# uLements_v2_5.net
KiCad netlist of a schematic drawn in EAGLE
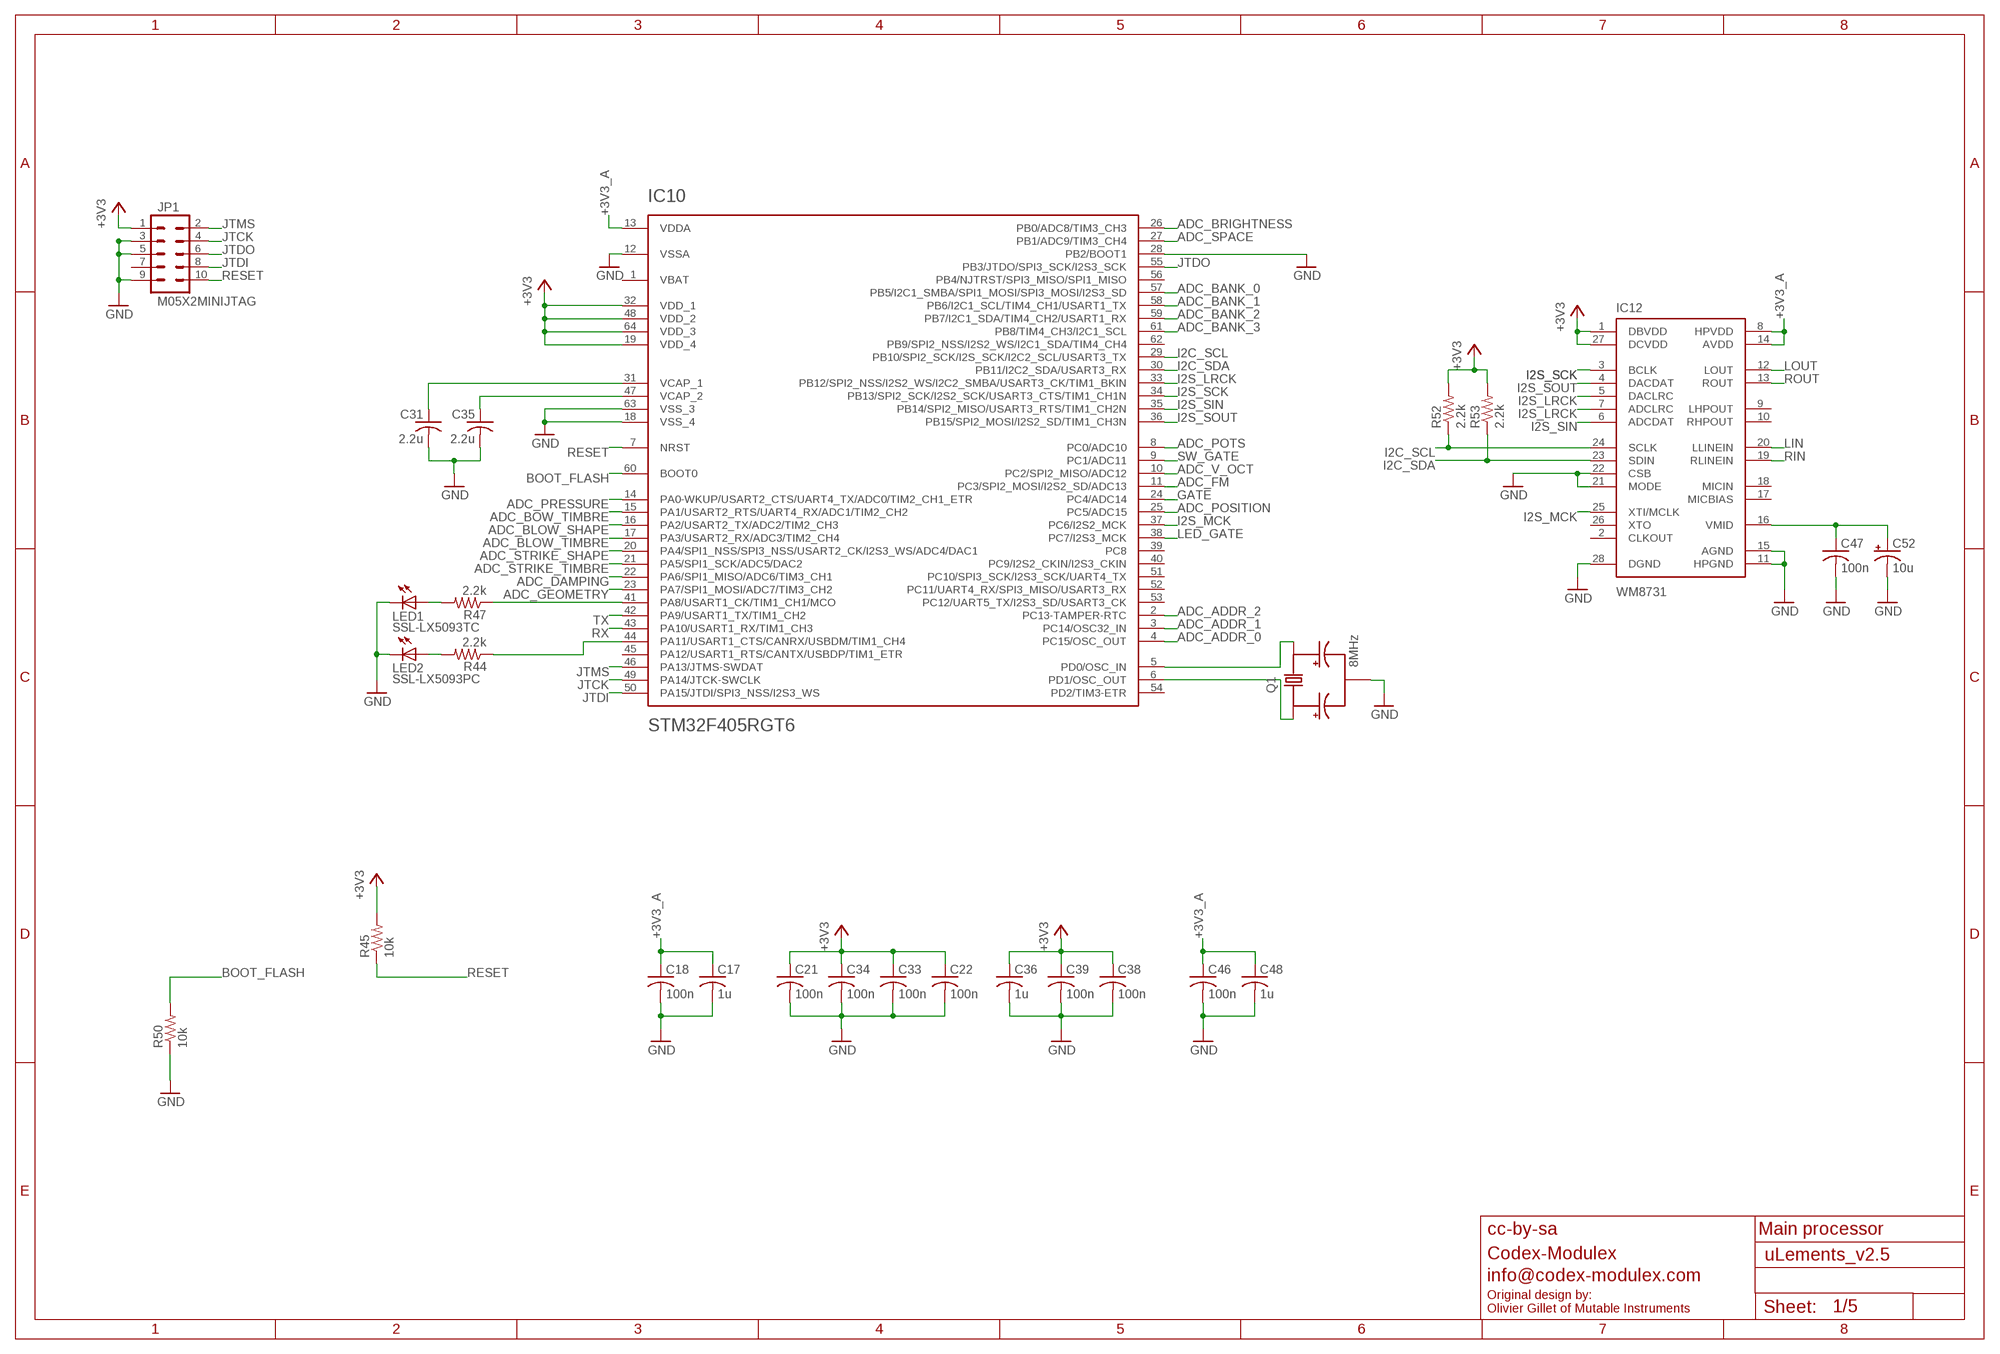
[diagram p0: schematic, sheet 1]
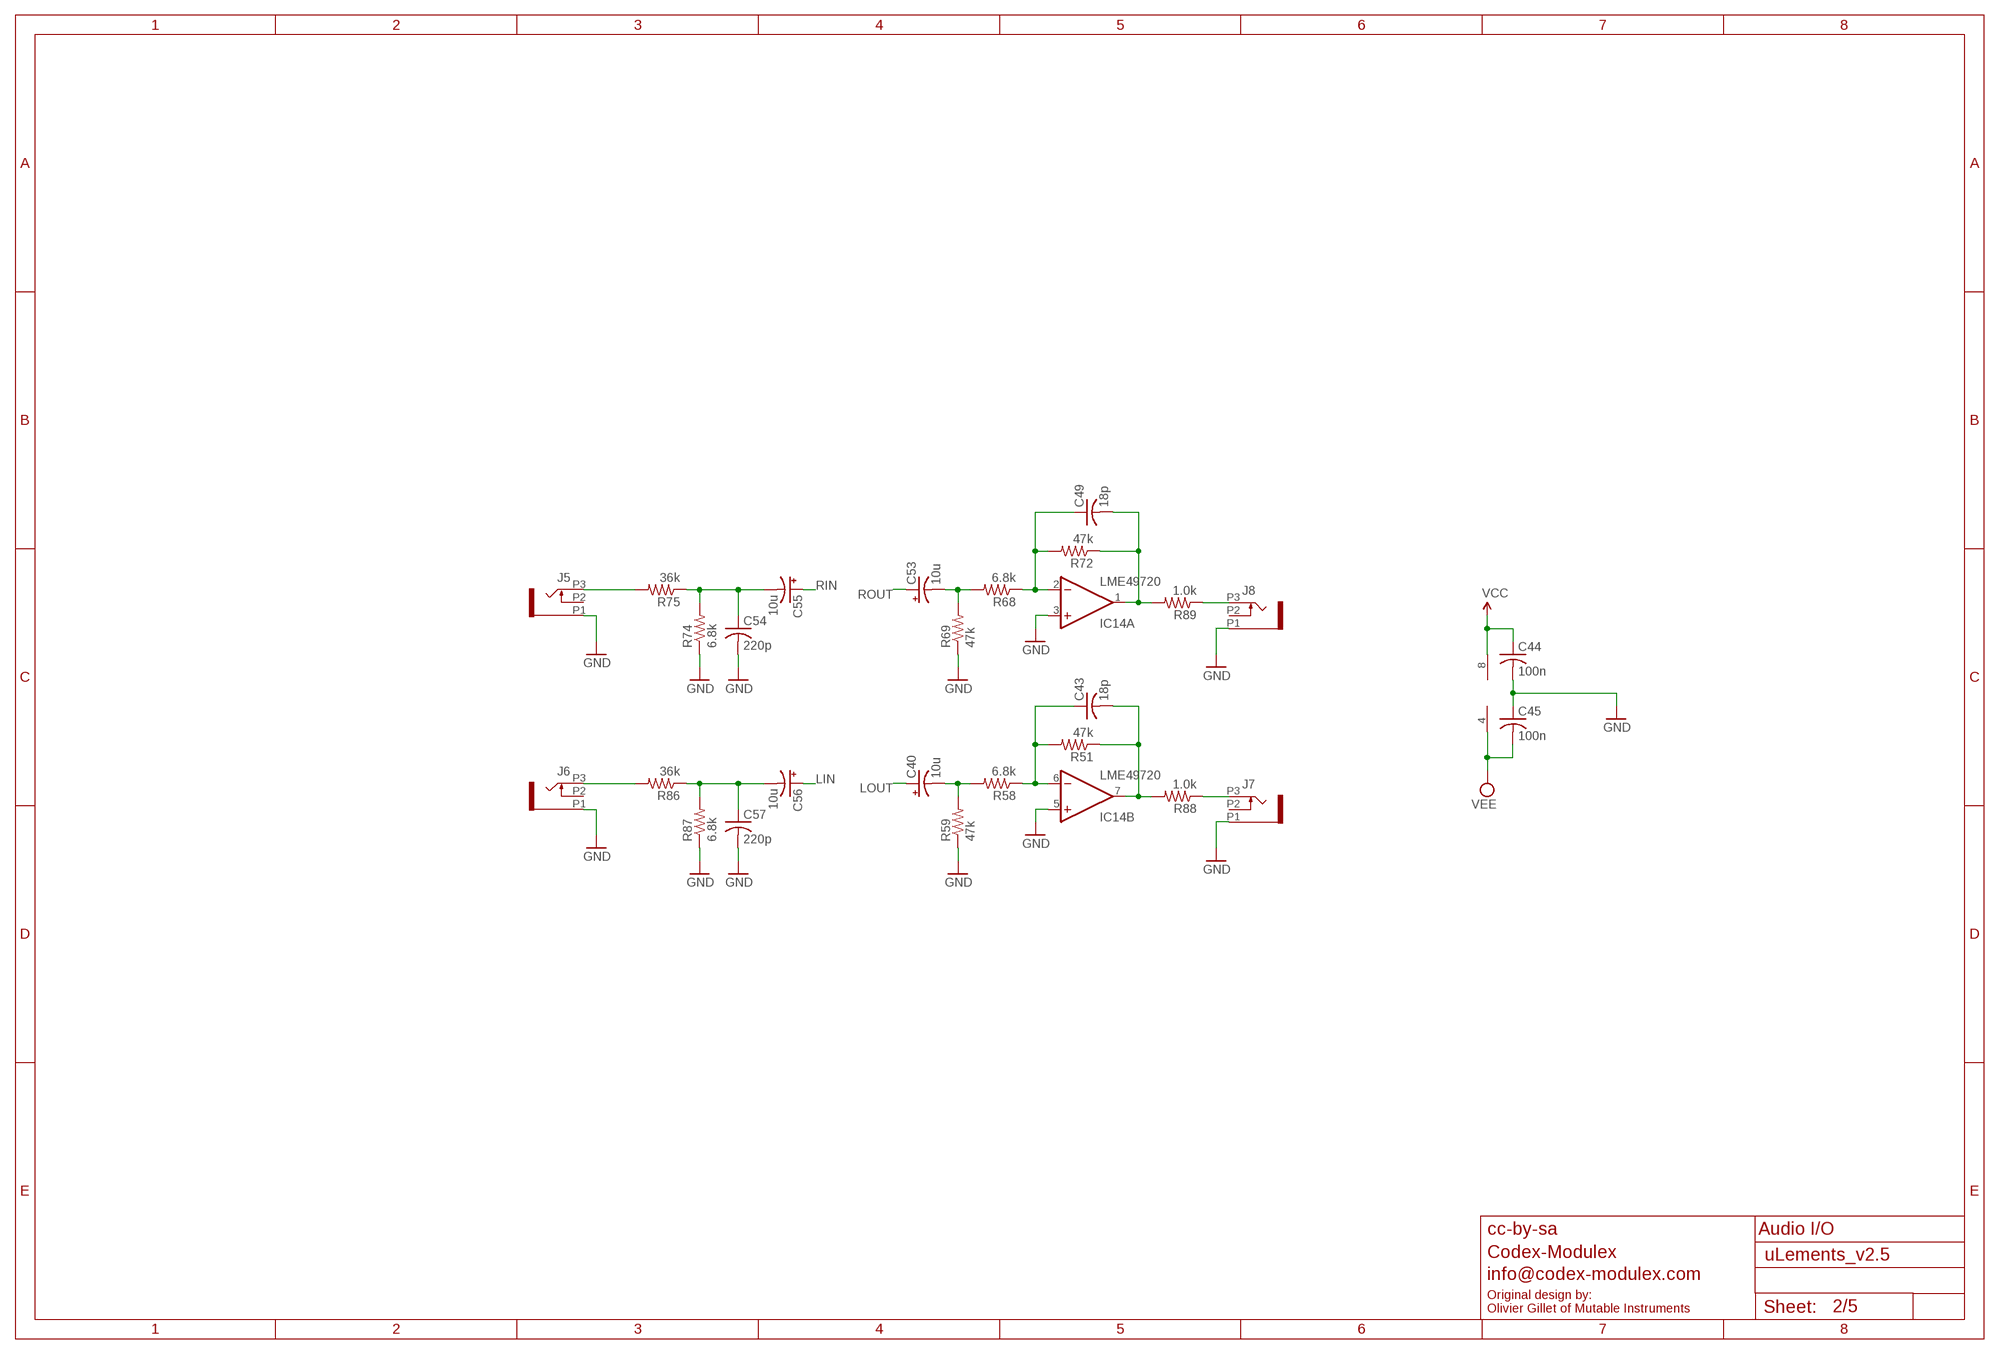
[diagram p1: schematic, sheet 2]
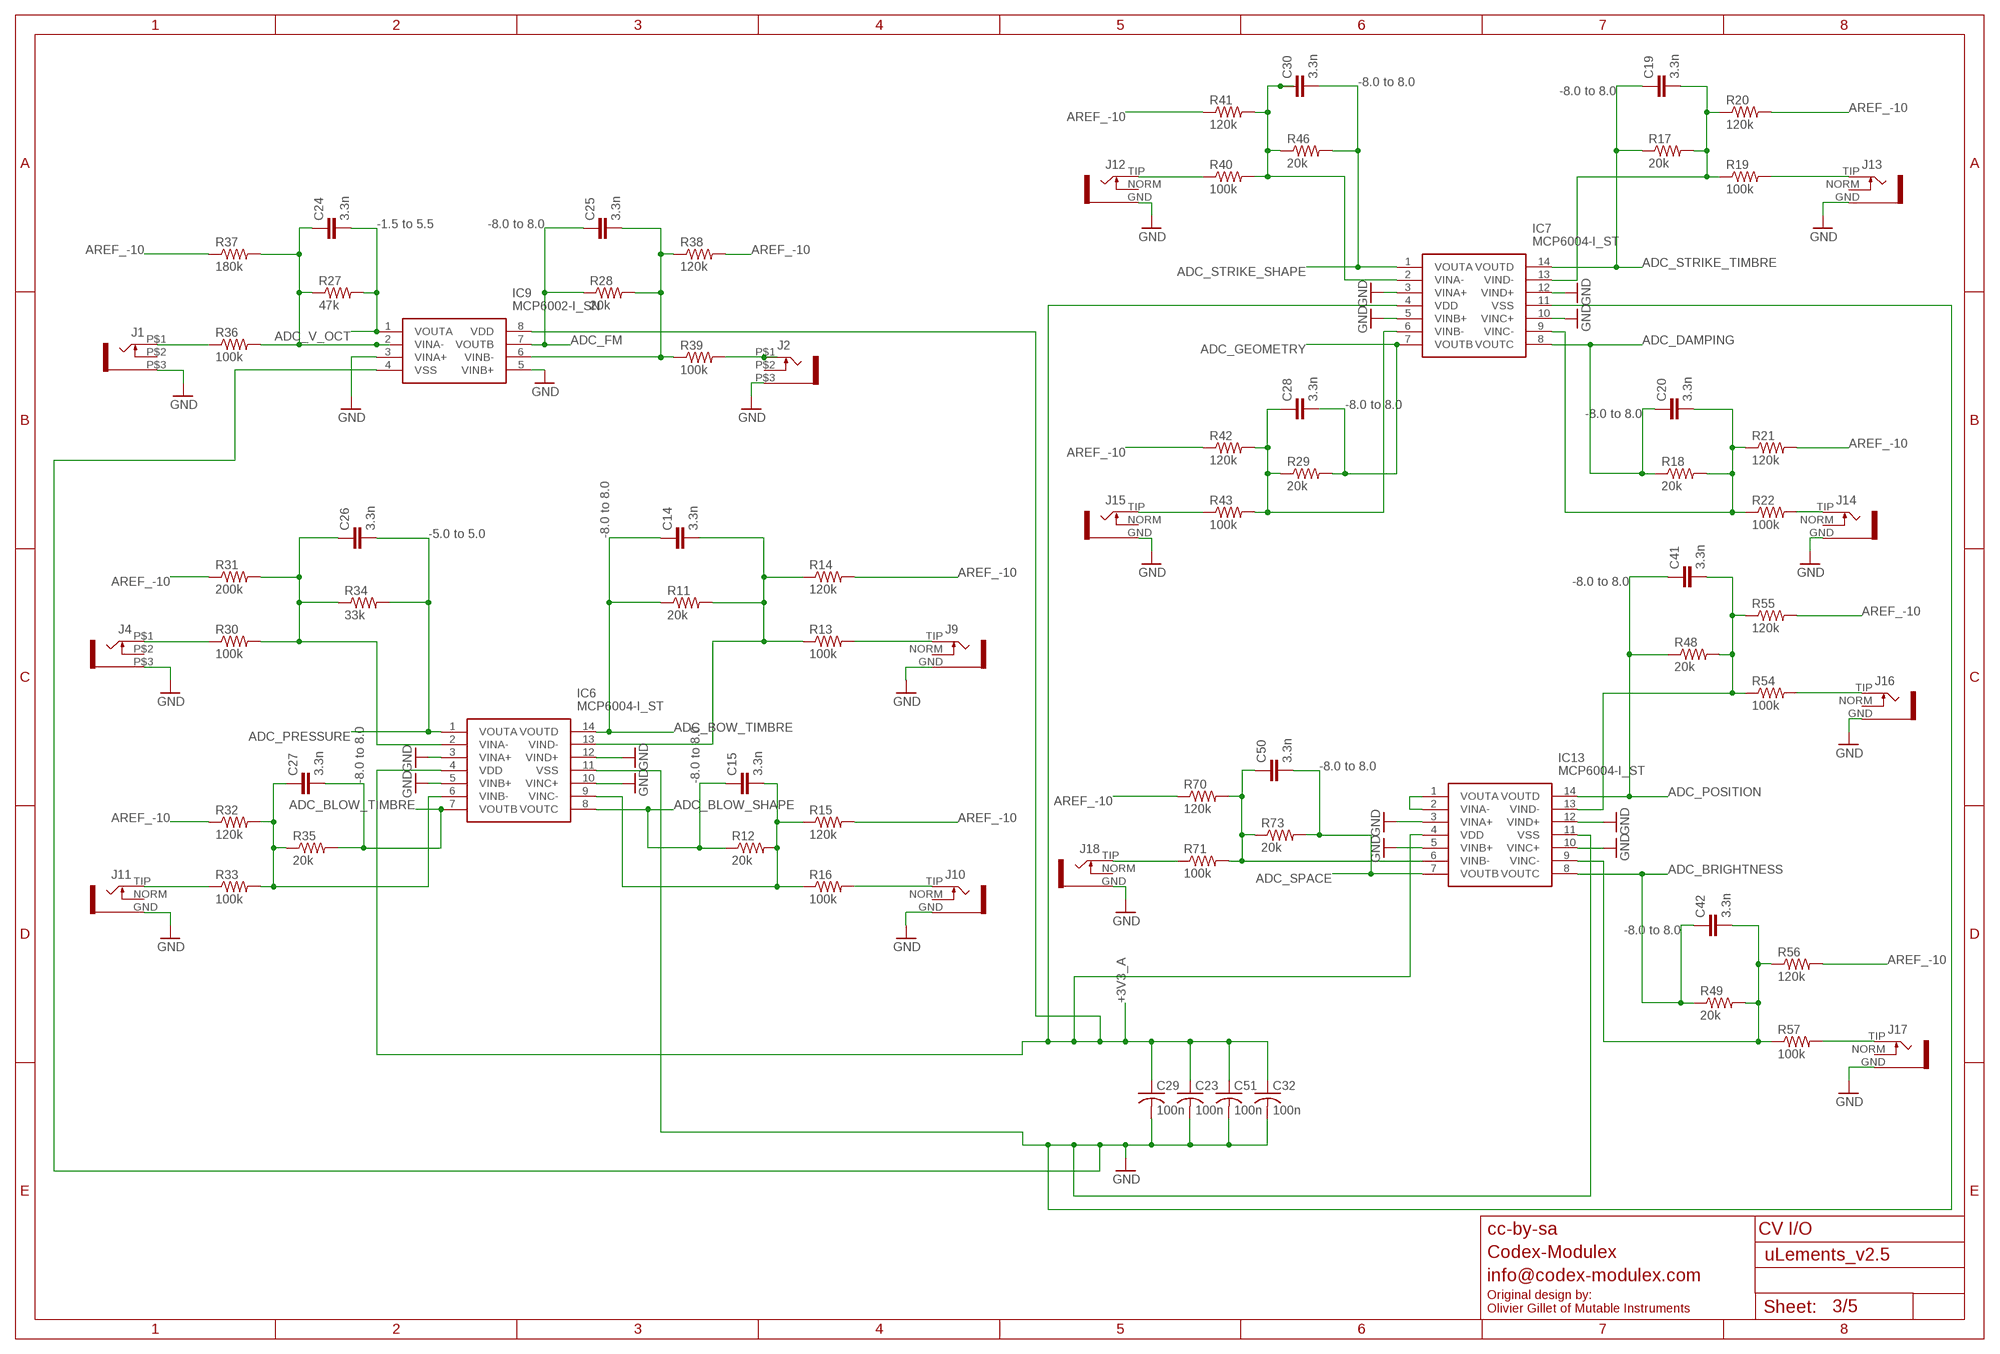
[diagram p2: schematic, sheet 3]
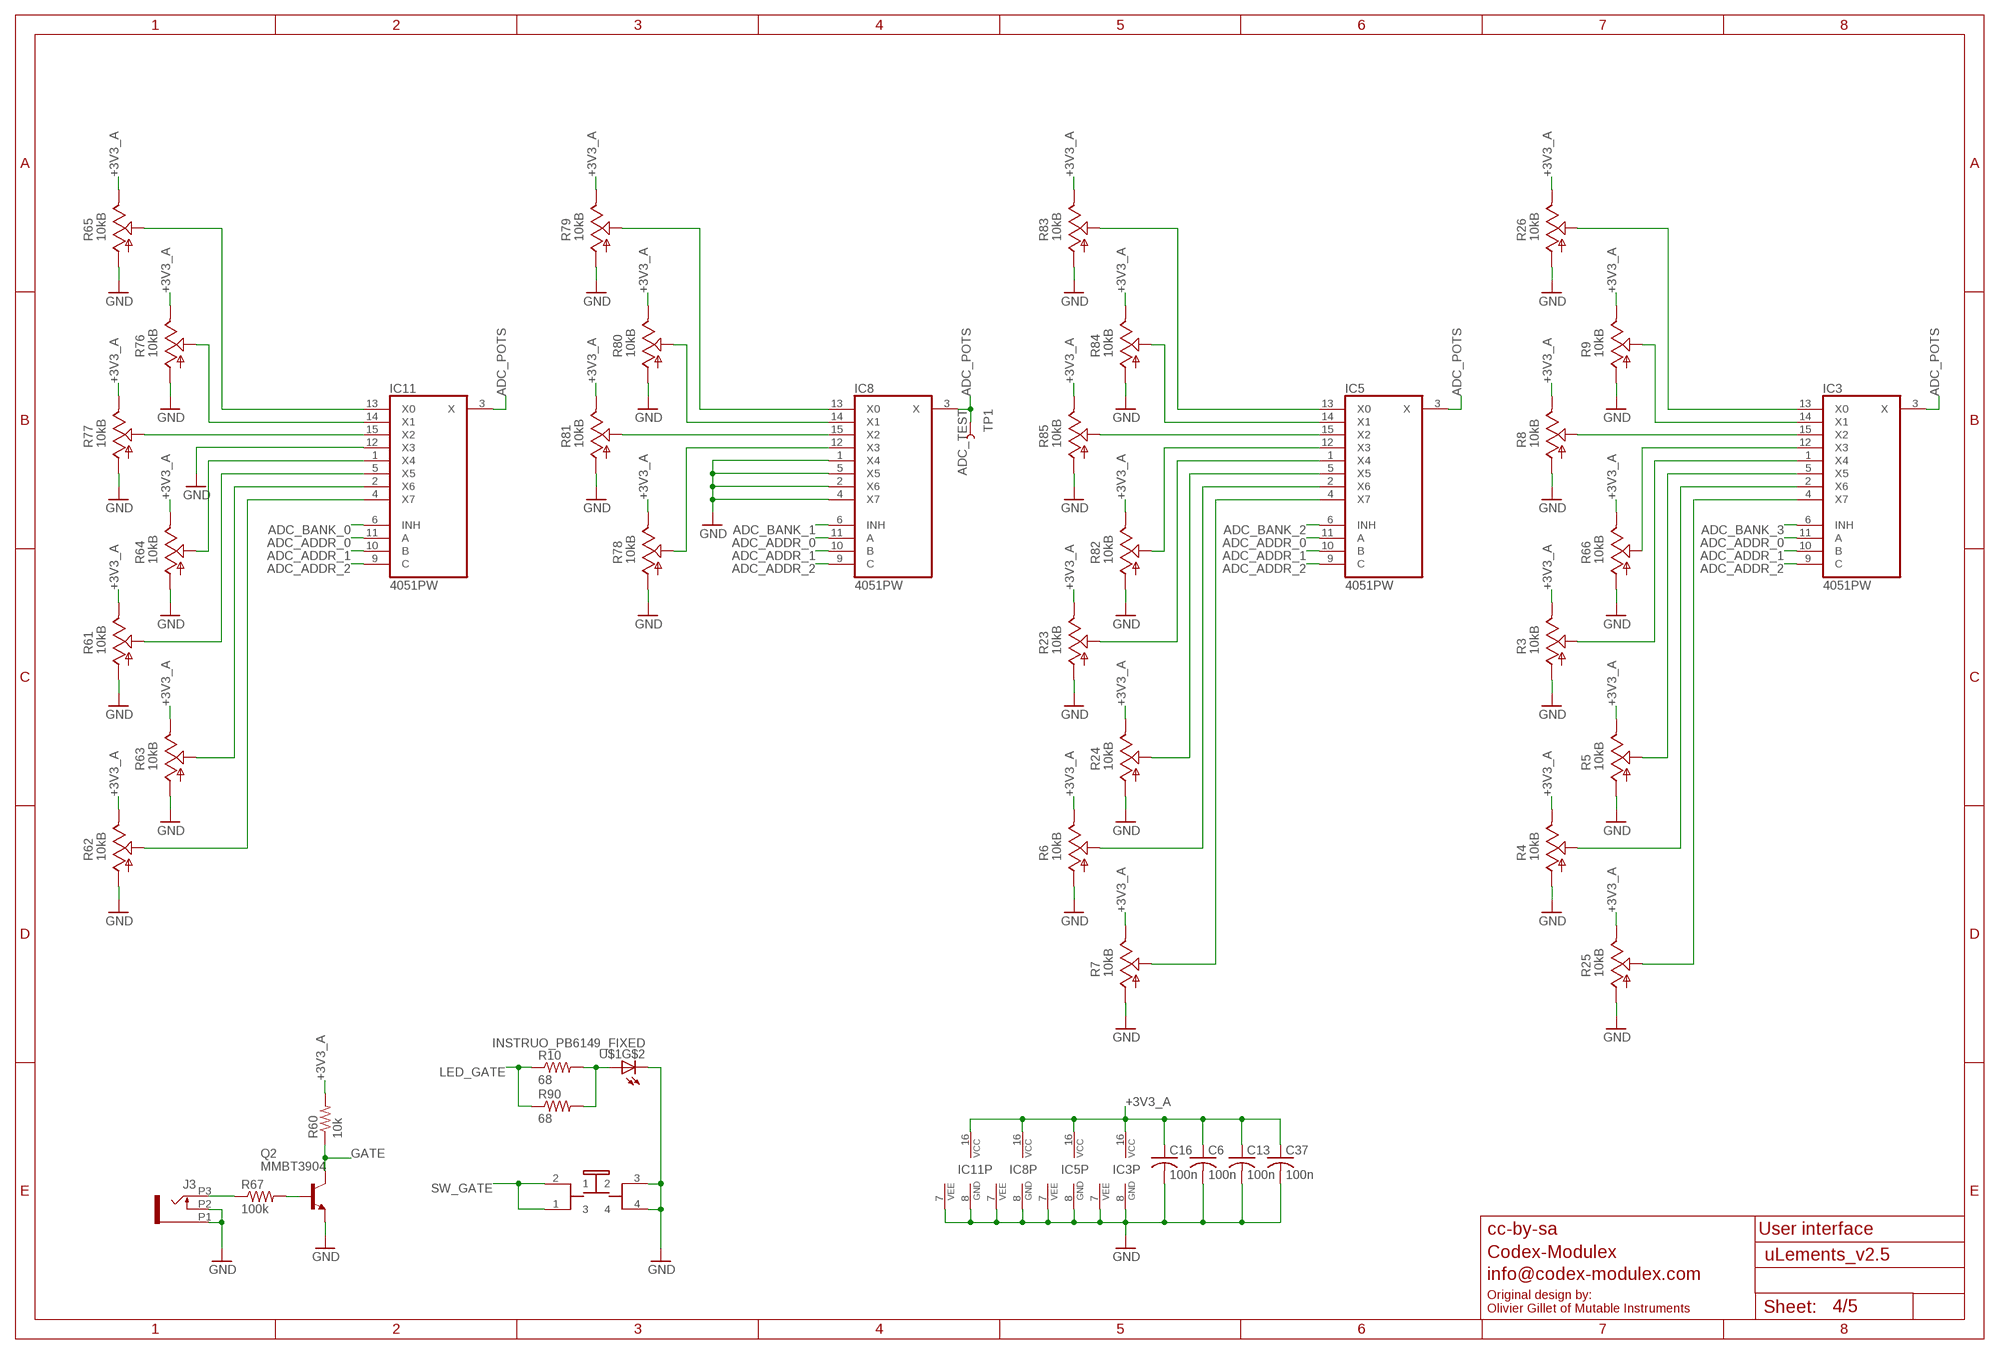
[diagram p3: schematic, sheet 4]
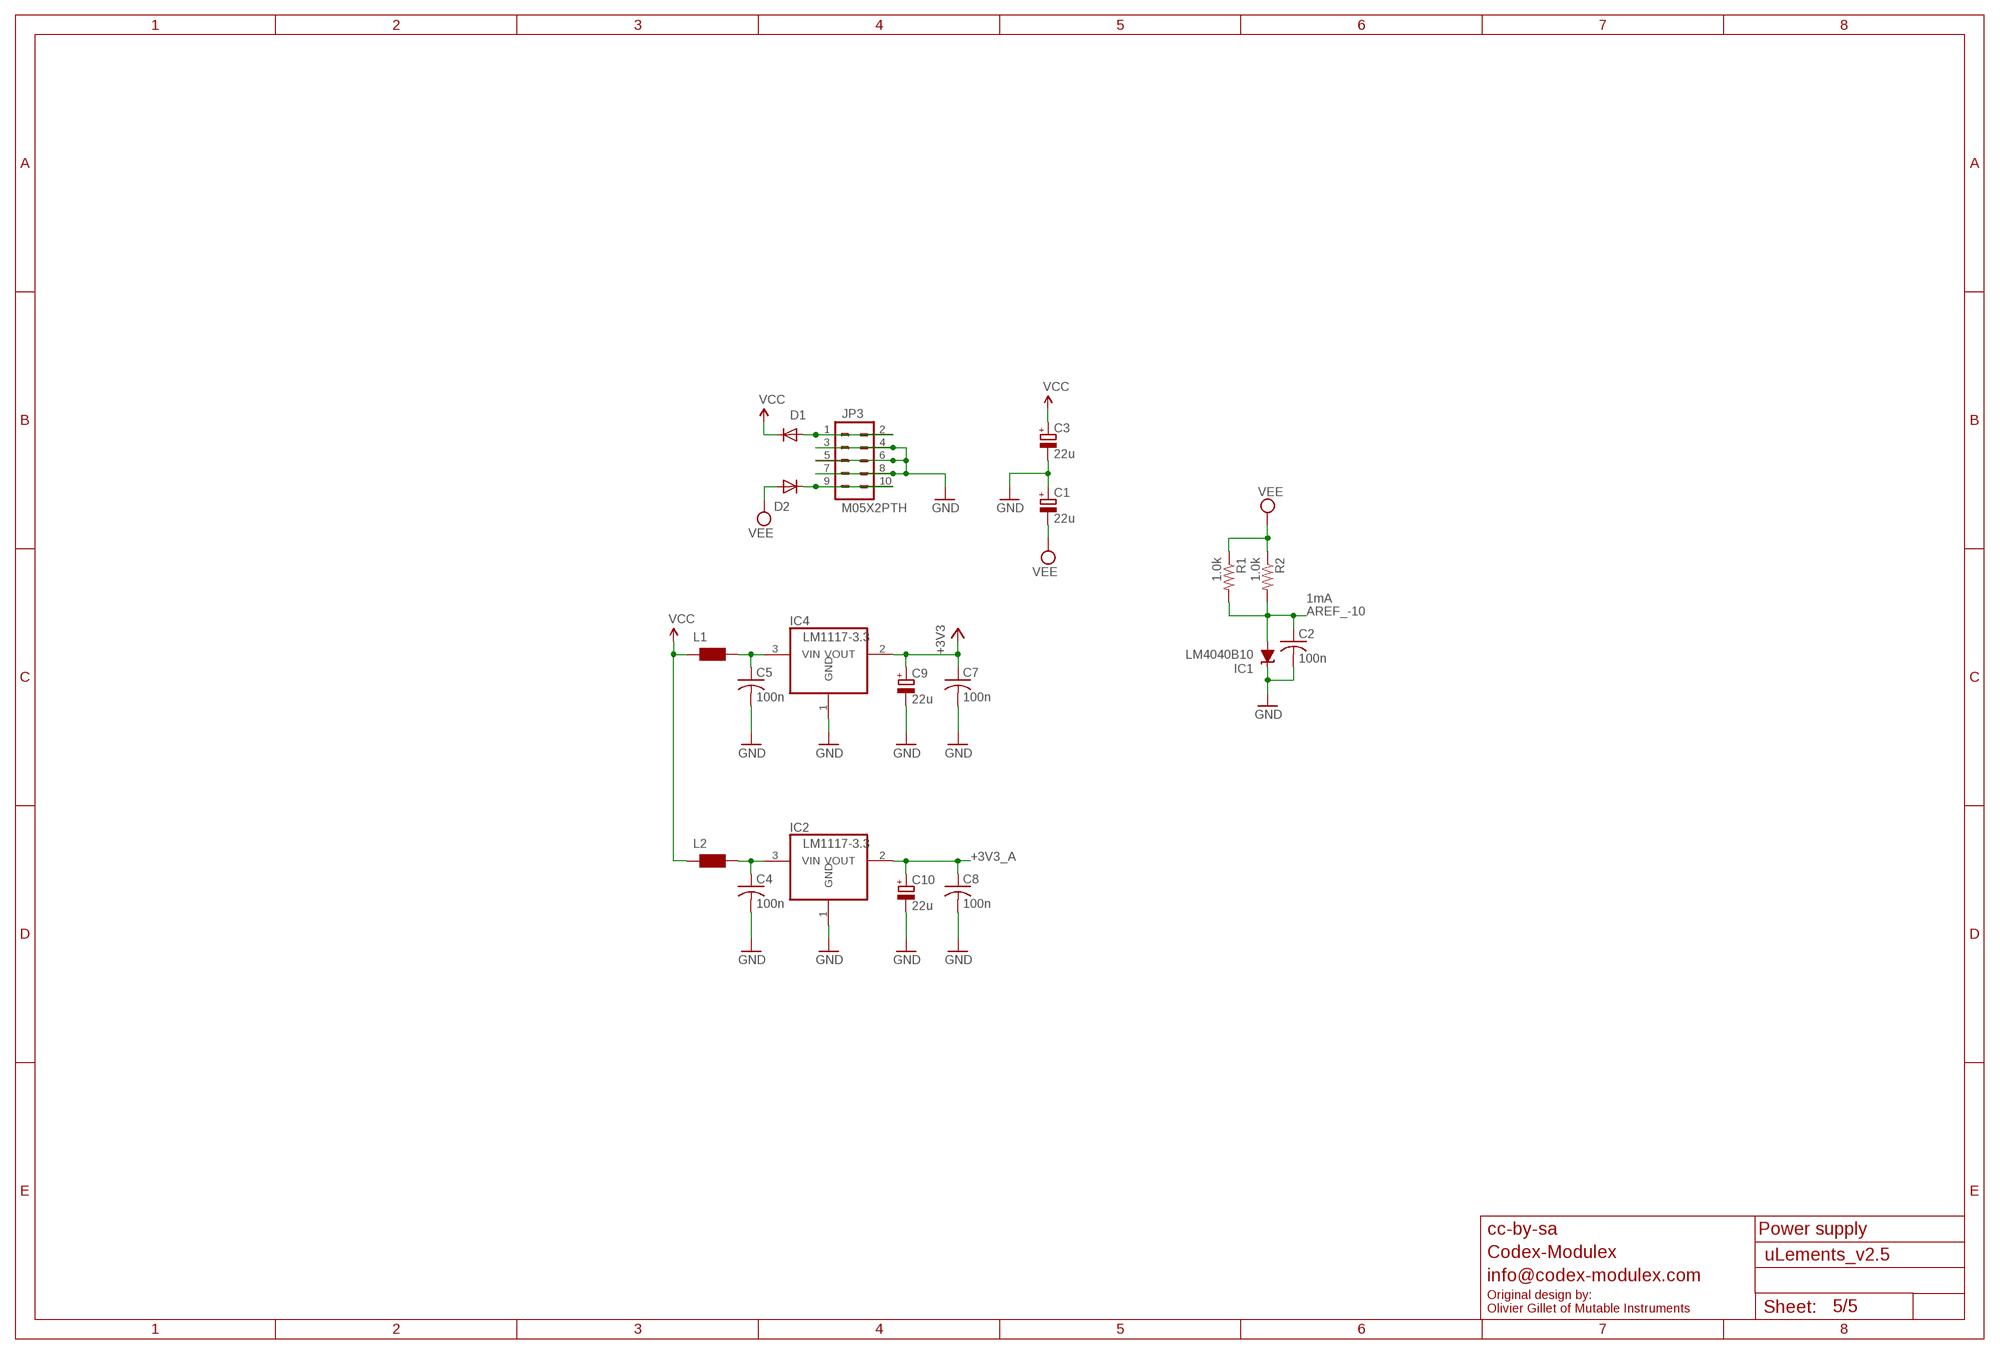
[diagram p4: schematic, sheet 5]

(export (version "E")
  (design (tool "Eeschema 10.0.6"))
  (components
    (comp (ref "C17")
      (value "1u")
      (footprint "eagle-import:C0603")
      (libsource (lib "eagle-import") (part "C-USC0603"))
    )
    (comp (ref "C18")
      (value "100n")
      (footprint "eagle-import:C0603")
      (libsource (lib "eagle-import") (part "C-USC0603"))
    )
    (comp (ref "C21")
      (value "100n")
      (footprint "eagle-import:C0603")
      (libsource (lib "eagle-import") (part "C-USC0603"))
    )
    (comp (ref "C22")
      (value "100n")
      (footprint "eagle-import:C0603")
      (libsource (lib "eagle-import") (part "C-USC0603"))
    )
    (comp (ref "C31")
      (value "2.2u")
      (footprint "eagle-import:C0805")
      (libsource (lib "eagle-import") (part "C-USC0805"))
    )
    (comp (ref "C33")
      (value "100n")
      (footprint "eagle-import:C0603")
      (libsource (lib "eagle-import") (part "C-USC0603"))
    )
    (comp (ref "C34")
      (value "100n")
      (footprint "eagle-import:C0603")
      (libsource (lib "eagle-import") (part "C-USC0603"))
    )
    (comp (ref "C35")
      (value "2.2u")
      (footprint "eagle-import:C0805")
      (libsource (lib "eagle-import") (part "C-USC0805"))
    )
    (comp (ref "C36")
      (value "1u")
      (footprint "eagle-import:C0603")
      (libsource (lib "eagle-import") (part "C-USC0603"))
    )
    (comp (ref "C38")
      (value "100n")
      (footprint "eagle-import:C0603")
      (libsource (lib "eagle-import") (part "C-USC0603"))
    )
    (comp (ref "C39")
      (value "100n")
      (footprint "eagle-import:C0603")
      (libsource (lib "eagle-import") (part "C-USC0603"))
    )
    (comp (ref "C46")
      (value "100n")
      (footprint "eagle-import:C0603")
      (libsource (lib "eagle-import") (part "C-USC0603"))
    )
    (comp (ref "C47")
      (value "100n")
      (footprint "eagle-import:C0603")
      (libsource (lib "eagle-import") (part "C-USC0603"))
    )
    (comp (ref "C48")
      (value "1u")
      (footprint "eagle-import:C0603")
      (libsource (lib "eagle-import") (part "C-USC0603"))
    )
    (comp (ref "C52")
      (value "10u")
      (footprint "eagle-import:PANASONIC_B")
      (libsource (lib "eagle-import") (part "CPOL-USB"))
    )
    (comp (ref "IC10")
      (value "STM32F405RGT6")
      (footprint "eagle-import:TQFP-10X10-64")
      (libsource (lib "eagle-import") (part "STM32F20X"))
    )
    (comp (ref "IC12")
      (value "WM8731")
      (footprint "eagle-import:SSOP28")
      (libsource (lib "eagle-import") (part "WM8731"))
    )
    (comp (ref "JP1")
      (value "M05X2MINIJTAG")
      (footprint "eagle-import:2X5-1.27")
      (libsource (lib "eagle-import") (part "M05X2MINIJTAG"))
    )
    (comp (ref "LED1")
      (value "SSL-LX5093TC")
      (footprint "eagle-import:LED5MM")
      (libsource (lib "eagle-import") (part "LED5MM"))
    )
    (comp (ref "LED2")
      (value "SSL-LX5093PC")
      (footprint "eagle-import:LED5MM")
      (libsource (lib "eagle-import") (part "LED5MM"))
    )
    (comp (ref "Q1")
      (value "8MHz")
      (footprint "eagle-import:INSTRUO_CRYSTAL_SMALLER")
      (libsource (lib "eagle-import") (part "INSTRUO_CRYSTAL_SMALLER"))
    )
    (comp (ref "R44")
      (value "2.2k")
      (footprint "eagle-import:R0603")
      (libsource (lib "eagle-import") (part "R-US_R0603"))
    )
    (comp (ref "R45")
      (value "10k")
      (footprint "eagle-import:R0603")
      (libsource (lib "eagle-import") (part "resistor_R-US_R0603"))
    )
    (comp (ref "R47")
      (value "2.2k")
      (footprint "eagle-import:R0603")
      (libsource (lib "eagle-import") (part "R-US_R0603"))
    )
    (comp (ref "R50")
      (value "10k")
      (footprint "eagle-import:R0603")
      (libsource (lib "eagle-import") (part "resistor_R-US_R0603"))
    )
    (comp (ref "R52")
      (value "2.2k")
      (footprint "eagle-import:R0603")
      (libsource (lib "eagle-import") (part "R-US_R0603"))
    )
    (comp (ref "R53")
      (value "2.2k")
      (footprint "eagle-import:R0603")
      (libsource (lib "eagle-import") (part "R-US_R0603"))
    )
    (comp (ref "C40")
      (value "10u")
      (footprint "eagle-import:PANASONIC_B")
      (libsource (lib "eagle-import") (part "CPOL-USB"))
    )
    (comp (ref "C43")
      (value "18p")
      (footprint "eagle-import:C0603")
      (libsource (lib "eagle-import") (part "C-USC0603"))
    )
    (comp (ref "C44")
      (value "100n")
      (footprint "eagle-import:C0603")
      (libsource (lib "eagle-import") (part "C-USC0603"))
    )
    (comp (ref "C45")
      (value "100n")
      (footprint "eagle-import:C0603")
      (libsource (lib "eagle-import") (part "C-USC0603"))
    )
    (comp (ref "C49")
      (value "18p")
      (footprint "eagle-import:C0603")
      (libsource (lib "eagle-import") (part "C-USC0603"))
    )
    (comp (ref "C53")
      (value "10u")
      (footprint "eagle-import:PANASONIC_B")
      (libsource (lib "eagle-import") (part "CPOL-USB"))
    )
    (comp (ref "C54")
      (value "220p")
      (footprint "eagle-import:C0603")
      (libsource (lib "eagle-import") (part "C-USC0603"))
    )
    (comp (ref "C55")
      (value "10u")
      (footprint "eagle-import:PANASONIC_B")
      (libsource (lib "eagle-import") (part "CPOL-USB"))
    )
    (comp (ref "C56")
      (value "10u")
      (footprint "eagle-import:PANASONIC_B")
      (libsource (lib "eagle-import") (part "CPOL-USB"))
    )
    (comp (ref "C57")
      (value "220p")
      (footprint "eagle-import:C0603")
      (libsource (lib "eagle-import") (part "C-USC0603"))
    )
    (comp (ref "IC14")
      (value "LME49720")
      (footprint "eagle-import:SO08")
      (libsource (lib "eagle-import") (part "TL072D"))
    )
    (comp (ref "J5")
      (value "PJ301_THONKICONN6")
      (footprint "eagle-import:WQP_PJ_301M6")
      (libsource (lib "eagle-import") (part "PJ301_THONKICONN6"))
    )
    (comp (ref "J6")
      (value "PJ301_THONKICONN6")
      (footprint "eagle-import:WQP_PJ_301M6")
      (libsource (lib "eagle-import") (part "PJ301_THONKICONN6"))
    )
    (comp (ref "J7")
      (value "PJ301_THONKICONN6")
      (footprint "eagle-import:WQP_PJ_301M6")
      (libsource (lib "eagle-import") (part "PJ301_THONKICONN6"))
    )
    (comp (ref "J8")
      (value "PJ301_THONKICONN6")
      (footprint "eagle-import:WQP_PJ_301M6")
      (libsource (lib "eagle-import") (part "PJ301_THONKICONN6"))
    )
    (comp (ref "R51")
      (value "47k")
      (footprint "eagle-import:R0603")
      (libsource (lib "eagle-import") (part "R-US_R0603"))
    )
    (comp (ref "R58")
      (value "6.8k")
      (footprint "eagle-import:R0603")
      (libsource (lib "eagle-import") (part "R-US_R0603"))
    )
    (comp (ref "R59")
      (value "47k")
      (footprint "eagle-import:R0603")
      (libsource (lib "eagle-import") (part "R-US_R0603"))
    )
    (comp (ref "R68")
      (value "6.8k")
      (footprint "eagle-import:R0603")
      (libsource (lib "eagle-import") (part "R-US_R0603"))
    )
    (comp (ref "R69")
      (value "47k")
      (footprint "eagle-import:R0603")
      (libsource (lib "eagle-import") (part "R-US_R0603"))
    )
    (comp (ref "R72")
      (value "47k")
      (footprint "eagle-import:R0603")
      (libsource (lib "eagle-import") (part "R-US_R0603"))
    )
    (comp (ref "R74")
      (value "6.8k")
      (footprint "eagle-import:R0603")
      (libsource (lib "eagle-import") (part "R-US_R0603"))
    )
    (comp (ref "R75")
      (value "36k")
      (footprint "eagle-import:R0603")
      (libsource (lib "eagle-import") (part "R-US_R0603"))
    )
    (comp (ref "R86")
      (value "36k")
      (footprint "eagle-import:R0603")
      (libsource (lib "eagle-import") (part "R-US_R0603"))
    )
    (comp (ref "R87")
      (value "6.8k")
      (footprint "eagle-import:R0603")
      (libsource (lib "eagle-import") (part "R-US_R0603"))
    )
    (comp (ref "R88")
      (value "1.0k")
      (footprint "eagle-import:R0603")
      (libsource (lib "eagle-import") (part "R-US_R0603"))
    )
    (comp (ref "R89")
      (value "1.0k")
      (footprint "eagle-import:R0603")
      (libsource (lib "eagle-import") (part "R-US_R0603"))
    )
    (comp (ref "C6")
      (value "100n")
      (footprint "eagle-import:C0603")
      (libsource (lib "eagle-import") (part "C-USC0603"))
    )
    (comp (ref "C13")
      (value "100n")
      (footprint "eagle-import:C0603")
      (libsource (lib "eagle-import") (part "C-USC0603"))
    )
    (comp (ref "C16")
      (value "100n")
      (footprint "eagle-import:C0603")
      (libsource (lib "eagle-import") (part "C-USC0603"))
    )
    (comp (ref "C37")
      (value "100n")
      (footprint "eagle-import:C0603")
      (libsource (lib "eagle-import") (part "C-USC0603"))
    )
    (comp (ref "IC3")
      (value "4051PW")
      (footprint "eagle-import:TSSOP16")
      (libsource (lib "eagle-import") (part "4051PW"))
    )
    (comp (ref "IC5")
      (value "4051PW")
      (footprint "eagle-import:TSSOP16")
      (libsource (lib "eagle-import") (part "4051PW"))
    )
    (comp (ref "IC8")
      (value "4051PW")
      (footprint "eagle-import:TSSOP16")
      (libsource (lib "eagle-import") (part "4051PW"))
    )
    (comp (ref "IC11")
      (value "4051PW")
      (footprint "eagle-import:TSSOP16")
      (libsource (lib "eagle-import") (part "4051PW"))
    )
    (comp (ref "J3")
      (value "PJ301_THONKICONN6")
      (footprint "eagle-import:WQP_PJ_301M6")
      (libsource (lib "eagle-import") (part "PJ301_THONKICONN6"))
    )
    (comp (ref "Q2")
      (value "MMBT3904")
      (footprint "eagle-import:SOT23-BEC")
      (libsource (lib "eagle-import") (part "-NPN-SOT23-BECMMBT3904LT1"))
    )
    (comp (ref "R3")
      (value "10kB")
      (footprint "eagle-import:OG-POTS_ALPS_POT_VERTICAL")
      (libsource (lib "eagle-import") (part "OG-POTS_POT_USVERTICAL"))
    )
    (comp (ref "R4")
      (value "10kB")
      (footprint "eagle-import:OG-POTS_ALPS_POT_VERTICAL")
      (libsource (lib "eagle-import") (part "OG-POTS_POT_USVERTICAL"))
    )
    (comp (ref "R5")
      (value "10kB")
      (footprint "eagle-import:OG-POTS_ALPS_POT_VERTICAL")
      (libsource (lib "eagle-import") (part "OG-POTS_POT_USVERTICAL"))
    )
    (comp (ref "R6")
      (value "10kB")
      (footprint "eagle-import:OG-POTS_ALPS_POT_VERTICAL")
      (libsource (lib "eagle-import") (part "OG-POTS_POT_USVERTICAL"))
    )
    (comp (ref "R7")
      (value "10kB")
      (footprint "eagle-import:OG-POTS_ALPS_POT_VERTICAL")
      (libsource (lib "eagle-import") (part "OG-POTS_POT_USVERTICAL"))
    )
    (comp (ref "R8")
      (value "10kB")
      (footprint "eagle-import:OG-POTS_ALPS_POT_VERTICAL")
      (libsource (lib "eagle-import") (part "OG-POTS_POT_USVERTICAL"))
    )
    (comp (ref "R9")
      (value "10kB")
      (footprint "eagle-import:OG-POTS_ALPS_POT_VERTICAL")
      (libsource (lib "eagle-import") (part "OG-POTS_POT_USVERTICAL"))
    )
    (comp (ref "R10")
      (value "68")
      (footprint "eagle-import:R0603")
      (libsource (lib "eagle-import") (part "R-US_R0603"))
    )
    (comp (ref "R23")
      (value "10kB")
      (footprint "eagle-import:OG-POTS_ALPS_POT_VERTICAL")
      (libsource (lib "eagle-import") (part "OG-POTS_POT_USVERTICAL"))
    )
    (comp (ref "R24")
      (value "10kB")
      (footprint "eagle-import:OG-POTS_ALPS_POT_VERTICAL")
      (libsource (lib "eagle-import") (part "OG-POTS_POT_USVERTICAL"))
    )
    (comp (ref "R25")
      (value "10kB")
      (footprint "eagle-import:OG-POTS_ALPS_POT_VERTICAL")
      (libsource (lib "eagle-import") (part "OG-POTS_POT_USVERTICAL"))
    )
    (comp (ref "R26")
      (value "10kB")
      (footprint "eagle-import:OG-POTS_ALPS_POT_VERTICAL")
      (libsource (lib "eagle-import") (part "OG-POTS_POT_USVERTICAL"))
    )
    (comp (ref "R60")
      (value "10k")
      (footprint "eagle-import:R0603")
      (libsource (lib "eagle-import") (part "R-US_R0603"))
    )
    (comp (ref "R61")
      (value "10kB")
      (footprint "eagle-import:OG-POTS_ALPS_POT_VERTICAL")
      (libsource (lib "eagle-import") (part "OG-POTS_POT_USVERTICAL"))
    )
    (comp (ref "R62")
      (value "10kB")
      (footprint "eagle-import:OG-POTS_ALPS_POT_VERTICAL")
      (libsource (lib "eagle-import") (part "OG-POTS_POT_USVERTICAL"))
    )
    (comp (ref "R63")
      (value "10kB")
      (footprint "eagle-import:OG-POTS_ALPS_POT_VERTICAL")
      (libsource (lib "eagle-import") (part "OG-POTS_POT_USVERTICAL"))
    )
    (comp (ref "R64")
      (value "10kB")
      (footprint "eagle-import:OG-POTS_ALPS_POT_VERTICAL")
      (libsource (lib "eagle-import") (part "OG-POTS_POT_USVERTICAL"))
    )
    (comp (ref "R65")
      (value "10kB")
      (footprint "eagle-import:OG-POTS_ALPS_POT_VERTICAL")
      (libsource (lib "eagle-import") (part "OG-POTS_POT_USVERTICAL"))
    )
    (comp (ref "R66")
      (value "10kB")
      (footprint "eagle-import:OG-POTS_ALPS_POT_VERTICAL")
      (libsource (lib "eagle-import") (part "OG-POTS_POT_USVERTICAL"))
    )
    (comp (ref "R67")
      (value "100k")
      (footprint "eagle-import:R0603")
      (libsource (lib "eagle-import") (part "R-US_R0603"))
    )
    (comp (ref "R76")
      (value "10kB")
      (footprint "eagle-import:ALPS_POT_VERTICAL")
      (libsource (lib "eagle-import") (part "POT_USVERTICAL"))
    )
    (comp (ref "R77")
      (value "10kB")
      (footprint "eagle-import:ALPS_POT_VERTICAL")
      (libsource (lib "eagle-import") (part "POT_USVERTICAL"))
    )
    (comp (ref "R78")
      (value "10kB")
      (footprint "eagle-import:ALPS_POT_VERTICAL")
      (libsource (lib "eagle-import") (part "POT_USVERTICAL"))
    )
    (comp (ref "R79")
      (value "10kB")
      (footprint "eagle-import:ALPS_POT_VERTICAL")
      (libsource (lib "eagle-import") (part "POT_USVERTICAL"))
    )
    (comp (ref "R80")
      (value "10kB")
      (footprint "eagle-import:ALPS_POT_VERTICAL")
      (libsource (lib "eagle-import") (part "POT_USVERTICAL"))
    )
    (comp (ref "R81")
      (value "10kB")
      (footprint "eagle-import:ALPS_POT_VERTICAL")
      (libsource (lib "eagle-import") (part "POT_USVERTICAL"))
    )
    (comp (ref "R82")
      (value "10kB")
      (footprint "eagle-import:ALPS_POT_VERTICAL")
      (libsource (lib "eagle-import") (part "POT_USVERTICAL"))
    )
    (comp (ref "R83")
      (value "10kB")
      (footprint "eagle-import:ALPS_POT_VERTICAL")
      (libsource (lib "eagle-import") (part "POT_USVERTICAL"))
    )
    (comp (ref "R84")
      (value "10kB")
      (footprint "eagle-import:ALPS_POT_VERTICAL")
      (libsource (lib "eagle-import") (part "POT_USVERTICAL"))
    )
    (comp (ref "R85")
      (value "10kB")
      (footprint "eagle-import:ALPS_POT_VERTICAL")
      (libsource (lib "eagle-import") (part "POT_USVERTICAL"))
    )
    (comp (ref "R90")
      (value "68")
      (footprint "eagle-import:R0603")
      (libsource (lib "eagle-import") (part "R-US_R0603"))
    )
    (comp (ref "TP1")
      (value "ADC_TEST")
      (footprint "eagle-import:PAD.03X.03")
      (libsource (lib "eagle-import") (part "TEST-POINT3"))
    )
    (comp (ref "U$1")
      (value "INSTRUO_PB6149_FIXED")
      (footprint "eagle-import:INSTRUO_PB6149L")
      (libsource (lib "eagle-import") (part "INSTRUO_PB6149_FIXED"))
    )
    (comp (ref "C14")
      (value "3.3n")
      (footprint "eagle-import:C0603")
      (libsource (lib "eagle-import") (part "C-EUC0603"))
    )
    (comp (ref "C15")
      (value "3.3n")
      (footprint "eagle-import:C0603")
      (libsource (lib "eagle-import") (part "C-EUC0603"))
    )
    (comp (ref "C19")
      (value "3.3n")
      (footprint "eagle-import:C0603")
      (libsource (lib "eagle-import") (part "C-EUC0603"))
    )
    (comp (ref "C20")
      (value "3.3n")
      (footprint "eagle-import:C0603")
      (libsource (lib "eagle-import") (part "C-EUC0603"))
    )
    (comp (ref "C23")
      (value "100n")
      (footprint "eagle-import:C0603")
      (libsource (lib "eagle-import") (part "C-USC0603"))
    )
    (comp (ref "C24")
      (value "3.3n")
      (footprint "eagle-import:C0603")
      (libsource (lib "eagle-import") (part "C-EUC0603"))
    )
    (comp (ref "C25")
      (value "3.3n")
      (footprint "eagle-import:C0603")
      (libsource (lib "eagle-import") (part "C-EUC0603"))
    )
    (comp (ref "C26")
      (value "3.3n")
      (footprint "eagle-import:C0603")
      (libsource (lib "eagle-import") (part "C-EUC0603"))
    )
    (comp (ref "C27")
      (value "3.3n")
      (footprint "eagle-import:C0603")
      (libsource (lib "eagle-import") (part "C-EUC0603"))
    )
    (comp (ref "C28")
      (value "3.3n")
      (footprint "eagle-import:C0603")
      (libsource (lib "eagle-import") (part "C-EUC0603"))
    )
    (comp (ref "C29")
      (value "100n")
      (footprint "eagle-import:C0603")
      (libsource (lib "eagle-import") (part "C-USC0603"))
    )
    (comp (ref "C30")
      (value "3.3n")
      (footprint "eagle-import:C0603")
      (libsource (lib "eagle-import") (part "C-EUC0603"))
    )
    (comp (ref "C32")
      (value "100n")
      (footprint "eagle-import:C0603")
      (libsource (lib "eagle-import") (part "C-USC0603"))
    )
    (comp (ref "C41")
      (value "3.3n")
      (footprint "eagle-import:C0603")
      (libsource (lib "eagle-import") (part "C-EUC0603"))
    )
    (comp (ref "C42")
      (value "3.3n")
      (footprint "eagle-import:C0603")
      (libsource (lib "eagle-import") (part "C-EUC0603"))
    )
    (comp (ref "C50")
      (value "3.3n")
      (footprint "eagle-import:C0603")
      (libsource (lib "eagle-import") (part "C-EUC0603"))
    )
    (comp (ref "C51")
      (value "100n")
      (footprint "eagle-import:C0603")
      (libsource (lib "eagle-import") (part "C-USC0603"))
    )
    (comp (ref "IC6")
      (value "MCP6004-I_ST")
      (footprint "eagle-import:SOP65P640X120-14N")
      (fields
        (field (name "MANUFACTURER_PART_NUMBER") "MCP6004-I/ST")
        (field (name "MOUSER_PART_NUMBER") "579-MCP6004-I/ST")
      )
      (libsource (lib "eagle-import") (part "MCP6004-I_ST"))
    )
    (comp (ref "IC7")
      (value "MCP6004-I_ST")
      (footprint "eagle-import:SOP65P640X120-14N")
      (fields
        (field (name "MANUFACTURER_PART_NUMBER") "MCP6004-I/ST")
        (field (name "MOUSER_PART_NUMBER") "579-MCP6004-I/ST")
      )
      (libsource (lib "eagle-import") (part "MCP6004-I_ST"))
    )
    (comp (ref "IC9")
      (value "MCP6002-I_SN")
      (footprint "eagle-import:SOIC127P600X175-8N")
      (fields
        (field (name "MANUFACTURER_PART_NUMBER") "MCP6002-I/SN")
        (field (name "MOUSER_PART_NUMBER") "579-MCP6002-I/SN")
      )
      (libsource (lib "eagle-import") (part "MCP6002-I_SN"))
    )
    (comp (ref "IC13")
      (value "MCP6004-I_ST")
      (footprint "eagle-import:SOP65P640X120-14N")
      (fields
        (field (name "MANUFACTURER_PART_NUMBER") "MCP6004-I/ST")
        (field (name "MOUSER_PART_NUMBER") "579-MCP6004-I/ST")
      )
      (libsource (lib "eagle-import") (part "MCP6004-I_ST"))
    )
    (comp (ref "J1")
      (value "WQP-PJ301M-12_JACK")
      (footprint "eagle-import:WQP-PJ301M-12_JACK")
      (libsource (lib "eagle-import") (part "WQP-PJ301M-12_JACK"))
    )
    (comp (ref "J2")
      (value "WQP-PJ301M-12_JACK")
      (footprint "eagle-import:WQP-PJ301M-12_JACK")
      (libsource (lib "eagle-import") (part "WQP-PJ301M-12_JACK"))
    )
    (comp (ref "J4")
      (value "WQP-PJ301M-12_JACK")
      (footprint "eagle-import:WQP-PJ301M-12_JACK")
      (libsource (lib "eagle-import") (part "WQP-PJ301M-12_JACK"))
    )
    (comp (ref "J9")
      (value "INSTRUO_S_JACK_S2_INV")
      (footprint "eagle-import:INSTRUO_S_JACK_S2_INV")
      (libsource (lib "eagle-import") (part "INSTRUO_S_JACK_S2_INV"))
    )
    (comp (ref "J10")
      (value "INSTRUO_S_JACK_S2_INV")
      (footprint "eagle-import:INSTRUO_S_JACK_S2_INV")
      (libsource (lib "eagle-import") (part "INSTRUO_S_JACK_S2_INV"))
    )
    (comp (ref "J11")
      (value "INSTRUO_S_JACK_S2_INV")
      (footprint "eagle-import:INSTRUO_S_JACK_S2_INV")
      (libsource (lib "eagle-import") (part "INSTRUO_S_JACK_S2_INV"))
    )
    (comp (ref "J12")
      (value "INSTRUO_S_JACK_S2_INV")
      (footprint "eagle-import:INSTRUO_S_JACK_S2_INV")
      (libsource (lib "eagle-import") (part "INSTRUO_S_JACK_S2_INV"))
    )
    (comp (ref "J13")
      (value "INSTRUO_S_JACK_S2_INV")
      (footprint "eagle-import:INSTRUO_S_JACK_S2_INV")
      (libsource (lib "eagle-import") (part "INSTRUO_S_JACK_S2_INV"))
    )
    (comp (ref "J14")
      (value "INSTRUO_S_JACK_S2_INV")
      (footprint "eagle-import:INSTRUO_S_JACK_S2_INV")
      (libsource (lib "eagle-import") (part "INSTRUO_S_JACK_S2_INV"))
    )
    (comp (ref "J15")
      (value "INSTRUO_S_JACK_S2_INV")
      (footprint "eagle-import:INSTRUO_S_JACK_S2_INV")
      (libsource (lib "eagle-import") (part "INSTRUO_S_JACK_S2_INV"))
    )
    (comp (ref "J16")
      (value "INSTRUO_S_JACK_S2_INV")
      (footprint "eagle-import:INSTRUO_S_JACK_S2_INV")
      (libsource (lib "eagle-import") (part "INSTRUO_S_JACK_S2_INV"))
    )
    (comp (ref "J17")
      (value "INSTRUO_S_JACK_S2_INV")
      (footprint "eagle-import:INSTRUO_S_JACK_S2_INV")
      (libsource (lib "eagle-import") (part "INSTRUO_S_JACK_S2_INV"))
    )
    (comp (ref "J18")
      (value "INSTRUO_S_JACK_S2_INV")
      (footprint "eagle-import:INSTRUO_S_JACK_S2_INV")
      (libsource (lib "eagle-import") (part "INSTRUO_S_JACK_S2_INV"))
    )
    (comp (ref "R11")
      (value "20k")
      (footprint "eagle-import:R0603")
      (libsource (lib "eagle-import") (part "resistor_R-US_R0603"))
    )
    (comp (ref "R12")
      (value "20k")
      (footprint "eagle-import:R0603")
      (libsource (lib "eagle-import") (part "resistor_R-US_R0603"))
    )
    (comp (ref "R13")
      (value "100k")
      (footprint "eagle-import:R0603")
      (libsource (lib "eagle-import") (part "resistor_R-US_R0603"))
    )
    (comp (ref "R14")
      (value "120k")
      (footprint "eagle-import:R0603")
      (libsource (lib "eagle-import") (part "resistor_R-US_R0603"))
    )
    (comp (ref "R15")
      (value "120k")
      (footprint "eagle-import:R0603")
      (libsource (lib "eagle-import") (part "resistor_R-US_R0603"))
    )
    (comp (ref "R16")
      (value "100k")
      (footprint "eagle-import:R0603")
      (libsource (lib "eagle-import") (part "resistor_R-US_R0603"))
    )
    (comp (ref "R17")
      (value "20k")
      (footprint "eagle-import:R0603")
      (libsource (lib "eagle-import") (part "resistor_R-US_R0603"))
    )
    (comp (ref "R18")
      (value "20k")
      (footprint "eagle-import:R0603")
      (libsource (lib "eagle-import") (part "resistor_R-US_R0603"))
    )
    (comp (ref "R19")
      (value "100k")
      (footprint "eagle-import:R0603")
      (libsource (lib "eagle-import") (part "resistor_R-US_R0603"))
    )
    (comp (ref "R20")
      (value "120k")
      (footprint "eagle-import:R0603")
      (libsource (lib "eagle-import") (part "resistor_R-US_R0603"))
    )
    (comp (ref "R21")
      (value "120k")
      (footprint "eagle-import:R0603")
      (libsource (lib "eagle-import") (part "resistor_R-US_R0603"))
    )
    (comp (ref "R22")
      (value "100k")
      (footprint "eagle-import:R0603")
      (libsource (lib "eagle-import") (part "resistor_R-US_R0603"))
    )
    (comp (ref "R27")
      (value "47k")
      (footprint "eagle-import:R0603")
      (libsource (lib "eagle-import") (part "resistor_R-US_R0603"))
    )
    (comp (ref "R28")
      (value "20k")
      (footprint "eagle-import:R0603")
      (libsource (lib "eagle-import") (part "resistor_R-US_R0603"))
    )
    (comp (ref "R29")
      (value "20k")
      (footprint "eagle-import:R0603")
      (libsource (lib "eagle-import") (part "resistor_R-US_R0603"))
    )
    (comp (ref "R30")
      (value "100k")
      (footprint "eagle-import:R0603")
      (libsource (lib "eagle-import") (part "resistor_R-US_R0603"))
    )
    (comp (ref "R31")
      (value "200k")
      (footprint "eagle-import:R0603")
      (libsource (lib "eagle-import") (part "resistor_R-US_R0603"))
    )
    (comp (ref "R32")
      (value "120k")
      (footprint "eagle-import:R0603")
      (libsource (lib "eagle-import") (part "resistor_R-US_R0603"))
    )
    (comp (ref "R33")
      (value "100k")
      (footprint "eagle-import:R0603")
      (libsource (lib "eagle-import") (part "resistor_R-US_R0603"))
    )
    (comp (ref "R34")
      (value "33k")
      (footprint "eagle-import:R0603")
      (libsource (lib "eagle-import") (part "resistor_R-US_R0603"))
    )
    (comp (ref "R35")
      (value "20k")
      (footprint "eagle-import:R0603")
      (libsource (lib "eagle-import") (part "resistor_R-US_R0603"))
    )
    (comp (ref "R36")
      (value "100k")
      (footprint "eagle-import:R0603")
      (libsource (lib "eagle-import") (part "resistor_R-US_R0603"))
    )
    (comp (ref "R37")
      (value "180k")
      (footprint "eagle-import:R0603")
      (libsource (lib "eagle-import") (part "resistor_R-US_R0603"))
    )
    (comp (ref "R38")
      (value "120k")
      (footprint "eagle-import:R0603")
      (libsource (lib "eagle-import") (part "resistor_R-US_R0603"))
    )
    (comp (ref "R39")
      (value "100k")
      (footprint "eagle-import:R0603")
      (libsource (lib "eagle-import") (part "resistor_R-US_R0603"))
    )
    (comp (ref "R40")
      (value "100k")
      (footprint "eagle-import:R0603")
      (libsource (lib "eagle-import") (part "resistor_R-US_R0603"))
    )
    (comp (ref "R41")
      (value "120k")
      (footprint "eagle-import:R0603")
      (libsource (lib "eagle-import") (part "resistor_R-US_R0603"))
    )
    (comp (ref "R42")
      (value "120k")
      (footprint "eagle-import:R0603")
      (libsource (lib "eagle-import") (part "resistor_R-US_R0603"))
    )
    (comp (ref "R43")
      (value "100k")
      (footprint "eagle-import:R0603")
      (libsource (lib "eagle-import") (part "resistor_R-US_R0603"))
    )
    (comp (ref "R46")
      (value "20k")
      (footprint "eagle-import:R0603")
      (libsource (lib "eagle-import") (part "resistor_R-US_R0603"))
    )
    (comp (ref "R48")
      (value "20k")
      (footprint "eagle-import:R0603")
      (libsource (lib "eagle-import") (part "resistor_R-US_R0603"))
    )
    (comp (ref "R49")
      (value "20k")
      (footprint "eagle-import:R0603")
      (libsource (lib "eagle-import") (part "resistor_R-US_R0603"))
    )
    (comp (ref "R54")
      (value "100k")
      (footprint "eagle-import:R0603")
      (libsource (lib "eagle-import") (part "resistor_R-US_R0603"))
    )
    (comp (ref "R55")
      (value "120k")
      (footprint "eagle-import:R0603")
      (libsource (lib "eagle-import") (part "resistor_R-US_R0603"))
    )
    (comp (ref "R56")
      (value "120k")
      (footprint "eagle-import:R0603")
      (libsource (lib "eagle-import") (part "resistor_R-US_R0603"))
    )
    (comp (ref "R57")
      (value "100k")
      (footprint "eagle-import:R0603")
      (libsource (lib "eagle-import") (part "resistor_R-US_R0603"))
    )
    (comp (ref "R70")
      (value "120k")
      (footprint "eagle-import:R0603")
      (libsource (lib "eagle-import") (part "resistor_R-US_R0603"))
    )
    (comp (ref "R71")
      (value "100k")
      (footprint "eagle-import:R0603")
      (libsource (lib "eagle-import") (part "resistor_R-US_R0603"))
    )
    (comp (ref "R73")
      (value "20k")
      (footprint "eagle-import:R0603")
      (libsource (lib "eagle-import") (part "resistor_R-US_R0603"))
    )
    (comp (ref "C1")
      (value "22u")
      (footprint "eagle-import:PANASONIC_B")
      (libsource (lib "eagle-import") (part "CPOL-EUB"))
    )
    (comp (ref "C2")
      (value "100n")
      (footprint "eagle-import:C0603")
      (libsource (lib "eagle-import") (part "C-USC0603"))
    )
    (comp (ref "C3")
      (value "22u")
      (footprint "eagle-import:PANASONIC_B")
      (libsource (lib "eagle-import") (part "CPOL-EUB"))
    )
    (comp (ref "C4")
      (value "100n")
      (footprint "eagle-import:C0603")
      (libsource (lib "eagle-import") (part "C-USC0603"))
    )
    (comp (ref "C5")
      (value "100n")
      (footprint "eagle-import:C0603")
      (libsource (lib "eagle-import") (part "C-USC0603"))
    )
    (comp (ref "C7")
      (value "100n")
      (footprint "eagle-import:C0603")
      (libsource (lib "eagle-import") (part "C-USC0603"))
    )
    (comp (ref "C8")
      (value "100n")
      (footprint "eagle-import:C0603")
      (libsource (lib "eagle-import") (part "C-USC0603"))
    )
    (comp (ref "C9")
      (value "22u")
      (footprint "eagle-import:PANASONIC_B")
      (libsource (lib "eagle-import") (part "CPOL-EUB"))
    )
    (comp (ref "C10")
      (value "22u")
      (footprint "eagle-import:PANASONIC_B")
      (libsource (lib "eagle-import") (part "CPOL-EUB"))
    )
    (comp (ref "D1")
      (value "1N5819HW")
      (footprint "eagle-import:SOD123")
      (libsource (lib "eagle-import") (part "DIODE-SOD123"))
    )
    (comp (ref "D2")
      (value "1N5819HW")
      (footprint "eagle-import:SOD123")
      (libsource (lib "eagle-import") (part "DIODE-SOD123"))
    )
    (comp (ref "IC1")
      (value "LM4040B10")
      (footprint "eagle-import:DBZ_R-PDSO-G3")
      (libsource (lib "eagle-import") (part "LM4041DBZB12"))
    )
    (comp (ref "IC2")
      (value "LM1117-3.3")
      (footprint "eagle-import:SOT223")
      (libsource (lib "eagle-import") (part "REG1117"))
    )
    (comp (ref "IC4")
      (value "LM1117-3.3")
      (footprint "eagle-import:SOT223")
      (libsource (lib "eagle-import") (part "REG1117"))
    )
    (comp (ref "JP3")
      (value "M05X2PTH")
      (footprint "eagle-import:AVR_ICSP")
      (libsource (lib "eagle-import") (part "M05X2PTH"))
    )
    (comp (ref "L1")
      (value "WE-CBF_0603")
      (footprint "eagle-import:0603")
      (libsource (lib "eagle-import") (part "WE-CBF_0603"))
    )
    (comp (ref "L2")
      (value "WE-CBF_0603")
      (footprint "eagle-import:0603")
      (libsource (lib "eagle-import") (part "WE-CBF_0603"))
    )
    (comp (ref "R1")
      (value "1.0k")
      (footprint "eagle-import:R0603")
      (libsource (lib "eagle-import") (part "R-US_R0603"))
    )
    (comp (ref "R2")
      (value "1.0k")
      (footprint "eagle-import:R0603")
      (libsource (lib "eagle-import") (part "R-US_R0603"))
    )
  )
  (nets
    (net (code "1") (name "+3V3") (class "Default")
      (node (ref "C21") (pin "1") (pinfunction "1_1") (pintype "passive"))
      (node (ref "C22") (pin "1") (pinfunction "1_1") (pintype "passive"))
      (node (ref "C33") (pin "1") (pinfunction "1_1") (pintype "passive"))
      (node (ref "C34") (pin "1") (pinfunction "1_1") (pintype "passive"))
      (node (ref "C36") (pin "1") (pinfunction "1_1") (pintype "passive"))
      (node (ref "C38") (pin "1") (pinfunction "1_1") (pintype "passive"))
      (node (ref "C39") (pin "1") (pinfunction "1_1") (pintype "passive"))
      (node (ref "C7") (pin "1") (pinfunction "1_1") (pintype "passive"))
      (node (ref "C9") (pin "+") (pinfunction "+_+") (pintype "passive"))
      (node (ref "IC10") (pin "19") (pinfunction "VDD_4_19") (pintype "power_in"))
      (node (ref "IC10") (pin "32") (pinfunction "VDD_1_32") (pintype "power_in"))
      (node (ref "IC10") (pin "48") (pinfunction "VDD_2_48") (pintype "power_in"))
      (node (ref "IC10") (pin "64") (pinfunction "VDD_3_64") (pintype "power_in"))
      (node (ref "IC12") (pin "1") (pinfunction "DBVDD_1") (pintype "bidirectional"))
      (node (ref "IC12") (pin "27") (pinfunction "DCVDD_27") (pintype "bidirectional"))
      (node (ref "IC4") (pin "2") (pinfunction "VOUT_2") (pintype "output"))
      (node (ref "JP1") (pin "1") (pinfunction "1_1") (pintype "passive"))
      (node (ref "R45") (pin "2") (pinfunction "2_2") (pintype "passive"))
      (node (ref "R52") (pin "2") (pinfunction "2_2") (pintype "passive"))
      (node (ref "R53") (pin "2") (pinfunction "2_2") (pintype "passive"))
    )
    (net (code "2") (name "+3V3_A") (class "Default")
      (node (ref "C10") (pin "+") (pinfunction "+_+") (pintype "passive"))
      (node (ref "C13") (pin "1") (pinfunction "1_1") (pintype "passive"))
      (node (ref "C16") (pin "1") (pinfunction "1_1") (pintype "passive"))
      (node (ref "C17") (pin "1") (pinfunction "1_1") (pintype "passive"))
      (node (ref "C18") (pin "1") (pinfunction "1_1") (pintype "passive"))
      (node (ref "C23") (pin "1") (pinfunction "1_1") (pintype "passive"))
      (node (ref "C29") (pin "1") (pinfunction "1_1") (pintype "passive"))
      (node (ref "C32") (pin "1") (pinfunction "1_1") (pintype "passive"))
      (node (ref "C37") (pin "1") (pinfunction "1_1") (pintype "passive"))
      (node (ref "C46") (pin "1") (pinfunction "1_1") (pintype "passive"))
      (node (ref "C48") (pin "1") (pinfunction "1_1") (pintype "passive"))
      (node (ref "C51") (pin "1") (pinfunction "1_1") (pintype "passive"))
      (node (ref "C6") (pin "1") (pinfunction "1_1") (pintype "passive"))
      (node (ref "C8") (pin "1") (pinfunction "1_1") (pintype "passive"))
      (node (ref "IC10") (pin "13") (pinfunction "VDDA_13") (pintype "power_in"))
      (node (ref "IC11") (pin "16") (pinfunction "VCC_16") (pintype "power_in"))
      (node (ref "IC12") (pin "14") (pinfunction "AVDD_14") (pintype "bidirectional"))
      (node (ref "IC12") (pin "8") (pinfunction "HPVDD_8") (pintype "bidirectional"))
      (node (ref "IC13") (pin "4") (pinfunction "VDD_4") (pintype "power_in"))
      (node (ref "IC2") (pin "2") (pinfunction "VOUT_2") (pintype "output"))
      (node (ref "IC3") (pin "16") (pinfunction "VCC_16") (pintype "power_in"))
      (node (ref "IC5") (pin "16") (pinfunction "VCC_16") (pintype "power_in"))
      (node (ref "IC6") (pin "4") (pinfunction "VDD_4") (pintype "power_in"))
      (node (ref "IC7") (pin "4") (pinfunction "VDD_4") (pintype "power_in"))
      (node (ref "IC8") (pin "16") (pinfunction "VCC_16") (pintype "power_in"))
      (node (ref "IC9") (pin "8") (pinfunction "VDD_8") (pintype "power_in"))
      (node (ref "R23") (pin "P$1") (pinfunction "E_P$1") (pintype "passive"))
      (node (ref "R24") (pin "P$1") (pinfunction "E_P$1") (pintype "passive"))
      (node (ref "R25") (pin "P$1") (pinfunction "E_P$1") (pintype "passive"))
      (node (ref "R26") (pin "P$1") (pinfunction "E_P$1") (pintype "passive"))
      (node (ref "R3") (pin "P$1") (pinfunction "E_P$1") (pintype "passive"))
      (node (ref "R4") (pin "P$1") (pinfunction "E_P$1") (pintype "passive"))
      (node (ref "R5") (pin "P$1") (pinfunction "E_P$1") (pintype "passive"))
      (node (ref "R6") (pin "P$1") (pinfunction "E_P$1") (pintype "passive"))
      (node (ref "R60") (pin "2") (pinfunction "2_2") (pintype "passive"))
      (node (ref "R61") (pin "P$1") (pinfunction "E_P$1") (pintype "passive"))
      (node (ref "R62") (pin "P$1") (pinfunction "E_P$1") (pintype "passive"))
      (node (ref "R63") (pin "P$1") (pinfunction "E_P$1") (pintype "passive"))
      (node (ref "R64") (pin "P$1") (pinfunction "E_P$1") (pintype "passive"))
      (node (ref "R65") (pin "P$1") (pinfunction "E_P$1") (pintype "passive"))
      (node (ref "R66") (pin "P$1") (pinfunction "E_P$1") (pintype "passive"))
      (node (ref "R7") (pin "P$1") (pinfunction "E_P$1") (pintype "passive"))
      (node (ref "R76") (pin "P$1") (pinfunction "E_P$1") (pintype "passive"))
      (node (ref "R77") (pin "P$1") (pinfunction "E_P$1") (pintype "passive"))
      (node (ref "R78") (pin "P$1") (pinfunction "E_P$1") (pintype "passive"))
      (node (ref "R79") (pin "P$1") (pinfunction "E_P$1") (pintype "passive"))
      (node (ref "R8") (pin "P$1") (pinfunction "E_P$1") (pintype "passive"))
      (node (ref "R80") (pin "P$1") (pinfunction "E_P$1") (pintype "passive"))
      (node (ref "R81") (pin "P$1") (pinfunction "E_P$1") (pintype "passive"))
      (node (ref "R82") (pin "P$1") (pinfunction "E_P$1") (pintype "passive"))
      (node (ref "R83") (pin "P$1") (pinfunction "E_P$1") (pintype "passive"))
      (node (ref "R84") (pin "P$1") (pinfunction "E_P$1") (pintype "passive"))
      (node (ref "R85") (pin "P$1") (pinfunction "E_P$1") (pintype "passive"))
      (node (ref "R9") (pin "P$1") (pinfunction "E_P$1") (pintype "passive"))
    )
    (net (code "3") (name "ADC_ADDR_0") (class "Default")
      (node (ref "IC10") (pin "4") (pinfunction "PC15/OSC_OUT_4") (pintype "bidirectional"))
      (node (ref "IC11") (pin "11") (pinfunction "A_11") (pintype "input"))
      (node (ref "IC3") (pin "11") (pinfunction "A_11") (pintype "input"))
      (node (ref "IC5") (pin "11") (pinfunction "A_11") (pintype "input"))
      (node (ref "IC8") (pin "11") (pinfunction "A_11") (pintype "input"))
    )
    (net (code "4") (name "ADC_ADDR_1") (class "Default")
      (node (ref "IC10") (pin "3") (pinfunction "PC14/OSC32_IN_3") (pintype "bidirectional"))
      (node (ref "IC11") (pin "10") (pinfunction "B_10") (pintype "input"))
      (node (ref "IC3") (pin "10") (pinfunction "B_10") (pintype "input"))
      (node (ref "IC5") (pin "10") (pinfunction "B_10") (pintype "input"))
      (node (ref "IC8") (pin "10") (pinfunction "B_10") (pintype "input"))
    )
    (net (code "5") (name "ADC_ADDR_2") (class "Default")
      (node (ref "IC10") (pin "2") (pinfunction "PC13-TAMPER-RTC_2") (pintype "bidirectional"))
      (node (ref "IC11") (pin "9") (pinfunction "C_9") (pintype "input"))
      (node (ref "IC3") (pin "9") (pinfunction "C_9") (pintype "input"))
      (node (ref "IC5") (pin "9") (pinfunction "C_9") (pintype "input"))
      (node (ref "IC8") (pin "9") (pinfunction "C_9") (pintype "input"))
    )
    (net (code "6") (name "ADC_BANK_0") (class "Default")
      (node (ref "IC10") (pin "57") (pinfunction "PB5/I2C1_SMBA/SPI1_MOSI/SPI3_MOSI/I2S3_SD_57") (pintype "bidirectional"))
      (node (ref "IC11") (pin "6") (pinfunction "INH_6") (pintype "input"))
    )
    (net (code "7") (name "ADC_BANK_1") (class "Default")
      (node (ref "IC10") (pin "58") (pinfunction "PB6/I2C1_SCL/TIM4_CH1/USART1_TX_58") (pintype "bidirectional"))
      (node (ref "IC8") (pin "6") (pinfunction "INH_6") (pintype "input"))
    )
    (net (code "8") (name "ADC_BANK_2") (class "Default")
      (node (ref "IC10") (pin "59") (pinfunction "PB7/I2C1_SDA/TIM4_CH2/USART1_RX_59") (pintype "bidirectional"))
      (node (ref "IC5") (pin "6") (pinfunction "INH_6") (pintype "input"))
    )
    (net (code "9") (name "ADC_BANK_3") (class "Default")
      (node (ref "IC10") (pin "61") (pinfunction "PB8/TIM4_CH3/I2C1_SCL_61") (pintype "bidirectional"))
      (node (ref "IC3") (pin "6") (pinfunction "INH_6") (pintype "input"))
    )
    (net (code "10") (name "ADC_BLOW_SHAPE") (class "Default")
      (node (ref "C15") (pin "1") (pinfunction "1_1") (pintype "passive"))
      (node (ref "IC10") (pin "16") (pinfunction "PA2/USART2_TX/ADC2/TIM2_CH3_16") (pintype "bidirectional"))
      (node (ref "IC6") (pin "8") (pinfunction "VOUTC_8") (pintype "output"))
      (node (ref "R12") (pin "1") (pinfunction "1_1") (pintype "passive"))
    )
    (net (code "11") (name "ADC_BLOW_TIMBRE") (class "Default")
      (node (ref "C27") (pin "2") (pinfunction "2_2") (pintype "passive"))
      (node (ref "IC10") (pin "17") (pinfunction "PA3/USART2_RX/ADC3/TIM2_CH4_17") (pintype "bidirectional"))
      (node (ref "IC6") (pin "7") (pinfunction "VOUTB_7") (pintype "output"))
      (node (ref "R35") (pin "2") (pinfunction "2_2") (pintype "passive"))
    )
    (net (code "12") (name "ADC_BOW_TIMBRE") (class "Default")
      (node (ref "C14") (pin "1") (pinfunction "1_1") (pintype "passive"))
      (node (ref "IC10") (pin "15") (pinfunction "PA1/USART2_RTS/UART4_RX/ADC1/TIM2_CH2_15") (pintype "bidirectional"))
      (node (ref "IC6") (pin "14") (pinfunction "VOUTD_14") (pintype "output"))
      (node (ref "R11") (pin "1") (pinfunction "1_1") (pintype "passive"))
    )
    (net (code "13") (name "ADC_BRIGHTNESS") (class "Default")
      (node (ref "C42") (pin "1") (pinfunction "1_1") (pintype "passive"))
      (node (ref "IC10") (pin "26") (pinfunction "PB0/ADC8/TIM3_CH3_26") (pintype "bidirectional"))
      (node (ref "IC13") (pin "8") (pinfunction "VOUTC_8") (pintype "output"))
      (node (ref "R49") (pin "1") (pinfunction "1_1") (pintype "passive"))
    )
    (net (code "14") (name "ADC_DAMPING") (class "Default")
      (node (ref "C20") (pin "1") (pinfunction "1_1") (pintype "passive"))
      (node (ref "IC10") (pin "22") (pinfunction "PA6/SPI1_MISO/ADC6/TIM3_CH1_22") (pintype "bidirectional"))
      (node (ref "IC7") (pin "8") (pinfunction "VOUTC_8") (pintype "output"))
      (node (ref "R18") (pin "1") (pinfunction "1_1") (pintype "passive"))
    )
    (net (code "15") (name "ADC_FM") (class "Default")
      (node (ref "C25") (pin "1") (pinfunction "1_1") (pintype "passive"))
      (node (ref "IC10") (pin "11") (pinfunction "PC3/SPI2_MOSI/I2S2_SD/ADC13_11") (pintype "bidirectional"))
      (node (ref "IC9") (pin "7") (pinfunction "VOUTB_7") (pintype "output"))
      (node (ref "R28") (pin "1") (pinfunction "1_1") (pintype "passive"))
    )
    (net (code "16") (name "ADC_GEOMETRY") (class "Default")
      (node (ref "C28") (pin "2") (pinfunction "2_2") (pintype "passive"))
      (node (ref "IC10") (pin "23") (pinfunction "PA7/SPI1_MOSI/ADC7/TIM3_CH2_23") (pintype "bidirectional"))
      (node (ref "IC7") (pin "7") (pinfunction "VOUTB_7") (pintype "output"))
      (node (ref "R29") (pin "2") (pinfunction "2_2") (pintype "passive"))
    )
    (net (code "17") (name "ADC_POSITION") (class "Default")
      (node (ref "C41") (pin "1") (pinfunction "1_1") (pintype "passive"))
      (node (ref "IC10") (pin "25") (pinfunction "PC5/ADC15_25") (pintype "bidirectional"))
      (node (ref "IC13") (pin "14") (pinfunction "VOUTD_14") (pintype "output"))
      (node (ref "R48") (pin "1") (pinfunction "1_1") (pintype "passive"))
    )
    (net (code "18") (name "ADC_POTS") (class "Default")
      (node (ref "IC10") (pin "8") (pinfunction "PC0/ADC10_8") (pintype "bidirectional"))
      (node (ref "IC11") (pin "3") (pinfunction "X_3") (pintype "bidirectional"))
      (node (ref "IC3") (pin "3") (pinfunction "X_3") (pintype "bidirectional"))
      (node (ref "IC5") (pin "3") (pinfunction "X_3") (pintype "bidirectional"))
      (node (ref "IC8") (pin "3") (pinfunction "X_3") (pintype "bidirectional"))
      (node (ref "TP1") (pin "P$1") (pinfunction "1_P$1") (pintype "bidirectional"))
    )
    (net (code "19") (name "ADC_PRESSURE") (class "Default")
      (node (ref "C26") (pin "2") (pinfunction "2_2") (pintype "passive"))
      (node (ref "IC10") (pin "14") (pinfunction "PA0-WKUP/USART2_CTS/UART4_TX/ADC0/TIM2_CH1_ETR_14") (pintype "bidirectional"))
      (node (ref "IC6") (pin "1") (pinfunction "VOUTA_1") (pintype "output"))
      (node (ref "R34") (pin "2") (pinfunction "2_2") (pintype "passive"))
    )
    (net (code "20") (name "ADC_SPACE") (class "Default")
      (node (ref "C50") (pin "2") (pinfunction "2_2") (pintype "passive"))
      (node (ref "IC10") (pin "27") (pinfunction "PB1/ADC9/TIM3_CH4_27") (pintype "bidirectional"))
      (node (ref "IC13") (pin "7") (pinfunction "VOUTB_7") (pintype "output"))
      (node (ref "R73") (pin "2") (pinfunction "2_2") (pintype "passive"))
    )
    (net (code "21") (name "ADC_STRIKE_SHAPE") (class "Default")
      (node (ref "C30") (pin "2") (pinfunction "2_2") (pintype "passive"))
      (node (ref "IC10") (pin "20") (pinfunction "PA4/SPI1_NSS/SPI3_NSS/USART2_CK/I2S3_WS/ADC4/DAC1_20") (pintype "bidirectional"))
      (node (ref "IC7") (pin "1") (pinfunction "VOUTA_1") (pintype "output"))
      (node (ref "R46") (pin "2") (pinfunction "2_2") (pintype "passive"))
    )
    (net (code "22") (name "ADC_STRIKE_TIMBRE") (class "Default")
      (node (ref "C19") (pin "1") (pinfunction "1_1") (pintype "passive"))
      (node (ref "IC10") (pin "21") (pinfunction "PA5/SPI1_SCK/ADC5/DAC2_21") (pintype "bidirectional"))
      (node (ref "IC7") (pin "14") (pinfunction "VOUTD_14") (pintype "output"))
      (node (ref "R17") (pin "1") (pinfunction "1_1") (pintype "passive"))
    )
    (net (code "23") (name "ADC_V_OCT") (class "Default")
      (node (ref "C24") (pin "2") (pinfunction "2_2") (pintype "passive"))
      (node (ref "IC10") (pin "10") (pinfunction "PC2/SPI2_MISO/ADC12_10") (pintype "bidirectional"))
      (node (ref "IC9") (pin "1") (pinfunction "VOUTA_1") (pintype "output"))
      (node (ref "R27") (pin "2") (pinfunction "2_2") (pintype "passive"))
    )
    (net (code "24") (name "AREF_-10") (class "Default")
      (node (ref "C2") (pin "1") (pinfunction "1_1") (pintype "passive"))
      (node (ref "IC1") (pin "2") (pinfunction "A_2") (pintype "passive"))
      (node (ref "R1") (pin "2") (pinfunction "2_2") (pintype "passive"))
      (node (ref "R14") (pin "2") (pinfunction "2_2") (pintype "passive"))
      (node (ref "R15") (pin "2") (pinfunction "2_2") (pintype "passive"))
      (node (ref "R2") (pin "2") (pinfunction "2_2") (pintype "passive"))
      (node (ref "R20") (pin "2") (pinfunction "2_2") (pintype "passive"))
      (node (ref "R21") (pin "2") (pinfunction "2_2") (pintype "passive"))
      (node (ref "R31") (pin "1") (pinfunction "1_1") (pintype "passive"))
      (node (ref "R32") (pin "1") (pinfunction "1_1") (pintype "passive"))
      (node (ref "R37") (pin "1") (pinfunction "1_1") (pintype "passive"))
      (node (ref "R38") (pin "2") (pinfunction "2_2") (pintype "passive"))
      (node (ref "R41") (pin "1") (pinfunction "1_1") (pintype "passive"))
      (node (ref "R42") (pin "1") (pinfunction "1_1") (pintype "passive"))
      (node (ref "R55") (pin "2") (pinfunction "2_2") (pintype "passive"))
      (node (ref "R56") (pin "2") (pinfunction "2_2") (pintype "passive"))
      (node (ref "R70") (pin "1") (pinfunction "1_1") (pintype "passive"))
    )
    (net (code "25") (name "BOOT_FLASH") (class "Default")
      (node (ref "IC10") (pin "60") (pinfunction "BOOT0_60") (pintype "bidirectional"))
      (node (ref "R50") (pin "2") (pinfunction "2_2") (pintype "passive"))
    )
    (net (code "26") (name "GATE") (class "Default")
      (node (ref "IC10") (pin "24") (pinfunction "PC4/ADC14_24") (pintype "bidirectional"))
      (node (ref "Q2") (pin "C") (pinfunction "C_C") (pintype "passive"))
      (node (ref "R60") (pin "1") (pinfunction "1_1") (pintype "passive"))
    )
    (net (code "27") (name "GND") (class "Default")
      (node (ref "C1") (pin "+") (pinfunction "+_+") (pintype "passive"))
      (node (ref "C10") (pin "-") (pinfunction "-_-") (pintype "passive"))
      (node (ref "C13") (pin "2") (pinfunction "2_2") (pintype "passive"))
      (node (ref "C16") (pin "2") (pinfunction "2_2") (pintype "passive"))
      (node (ref "C17") (pin "2") (pinfunction "2_2") (pintype "passive"))
      (node (ref "C18") (pin "2") (pinfunction "2_2") (pintype "passive"))
      (node (ref "C2") (pin "2") (pinfunction "2_2") (pintype "passive"))
      (node (ref "C21") (pin "2") (pinfunction "2_2") (pintype "passive"))
      (node (ref "C22") (pin "2") (pinfunction "2_2") (pintype "passive"))
      (node (ref "C23") (pin "2") (pinfunction "2_2") (pintype "passive"))
      (node (ref "C29") (pin "2") (pinfunction "2_2") (pintype "passive"))
      (node (ref "C3") (pin "-") (pinfunction "-_-") (pintype "passive"))
      (node (ref "C31") (pin "2") (pinfunction "2_2") (pintype "passive"))
      (node (ref "C32") (pin "2") (pinfunction "2_2") (pintype "passive"))
      (node (ref "C33") (pin "2") (pinfunction "2_2") (pintype "passive"))
      (node (ref "C34") (pin "2") (pinfunction "2_2") (pintype "passive"))
      (node (ref "C35") (pin "2") (pinfunction "2_2") (pintype "passive"))
      (node (ref "C36") (pin "2") (pinfunction "2_2") (pintype "passive"))
      (node (ref "C37") (pin "2") (pinfunction "2_2") (pintype "passive"))
      (node (ref "C38") (pin "2") (pinfunction "2_2") (pintype "passive"))
      (node (ref "C39") (pin "2") (pinfunction "2_2") (pintype "passive"))
      (node (ref "C4") (pin "2") (pinfunction "2_2") (pintype "passive"))
      (node (ref "C44") (pin "2") (pinfunction "2_2") (pintype "passive"))
      (node (ref "C45") (pin "1") (pinfunction "1_1") (pintype "passive"))
      (node (ref "C46") (pin "2") (pinfunction "2_2") (pintype "passive"))
      (node (ref "C47") (pin "2") (pinfunction "2_2") (pintype "passive"))
      (node (ref "C48") (pin "2") (pinfunction "2_2") (pintype "passive"))
      (node (ref "C5") (pin "2") (pinfunction "2_2") (pintype "passive"))
      (node (ref "C51") (pin "2") (pinfunction "2_2") (pintype "passive"))
      (node (ref "C52") (pin "-") (pinfunction "-_-") (pintype "passive"))
      (node (ref "C54") (pin "2") (pinfunction "2_2") (pintype "passive"))
      (node (ref "C57") (pin "2") (pinfunction "2_2") (pintype "passive"))
      (node (ref "C6") (pin "2") (pinfunction "2_2") (pintype "passive"))
      (node (ref "C7") (pin "2") (pinfunction "2_2") (pintype "passive"))
      (node (ref "C8") (pin "2") (pinfunction "2_2") (pintype "passive"))
      (node (ref "C9") (pin "-") (pinfunction "-_-") (pintype "passive"))
      (node (ref "IC1") (pin "1") (pinfunction "C_1") (pintype "passive"))
      (node (ref "IC10") (pin "12") (pinfunction "VSSA_12") (pintype "power_in"))
      (node (ref "IC10") (pin "18") (pinfunction "VSS_4_18") (pintype "power_in"))
      (node (ref "IC10") (pin "28") (pinfunction "PB2/BOOT1_28") (pintype "bidirectional"))
      (node (ref "IC10") (pin "63") (pinfunction "VSS_3_63") (pintype "power_in"))
      (node (ref "IC11") (pin "12") (pinfunction "X3_12") (pintype "bidirectional"))
      (node (ref "IC11") (pin "7") (pinfunction "VEE_7") (pintype "power_in"))
      (node (ref "IC11") (pin "8") (pinfunction "GND_8") (pintype "power_in"))
      (node (ref "IC12") (pin "11") (pinfunction "HPGND_11") (pintype "bidirectional"))
      (node (ref "IC12") (pin "15") (pinfunction "AGND_15") (pintype "bidirectional"))
      (node (ref "IC12") (pin "21") (pinfunction "MODE_21") (pintype "bidirectional"))
      (node (ref "IC12") (pin "22") (pinfunction "CSB_22") (pintype "bidirectional"))
      (node (ref "IC12") (pin "28") (pinfunction "DGND_28") (pintype "bidirectional"))
      (node (ref "IC13") (pin "10") (pinfunction "VINC+_10") (pintype "input"))
      (node (ref "IC13") (pin "11") (pinfunction "VSS_11") (pintype "power_in"))
      (node (ref "IC13") (pin "12") (pinfunction "VIND+_12") (pintype "input"))
      (node (ref "IC13") (pin "3") (pinfunction "VINA+_3") (pintype "input"))
      (node (ref "IC13") (pin "5") (pinfunction "VINB+_5") (pintype "input"))
      (node (ref "IC14") (pin "3") (pinfunction "+IN_3") (pintype "input"))
      (node (ref "IC14") (pin "5") (pinfunction "+IN_5") (pintype "input"))
      (node (ref "IC2") (pin "1") (pinfunction "GND_1") (pintype "power_in"))
      (node (ref "IC3") (pin "7") (pinfunction "VEE_7") (pintype "power_in"))
      (node (ref "IC3") (pin "8") (pinfunction "GND_8") (pintype "power_in"))
      (node (ref "IC4") (pin "1") (pinfunction "GND_1") (pintype "power_in"))
      (node (ref "IC5") (pin "7") (pinfunction "VEE_7") (pintype "power_in"))
      (node (ref "IC5") (pin "8") (pinfunction "GND_8") (pintype "power_in"))
      (node (ref "IC6") (pin "10") (pinfunction "VINC+_10") (pintype "input"))
      (node (ref "IC6") (pin "11") (pinfunction "VSS_11") (pintype "power_in"))
      (node (ref "IC6") (pin "12") (pinfunction "VIND+_12") (pintype "input"))
      (node (ref "IC6") (pin "3") (pinfunction "VINA+_3") (pintype "input"))
      (node (ref "IC6") (pin "5") (pinfunction "VINB+_5") (pintype "input"))
      (node (ref "IC7") (pin "10") (pinfunction "VINC+_10") (pintype "input"))
      (node (ref "IC7") (pin "11") (pinfunction "VSS_11") (pintype "power_in"))
      (node (ref "IC7") (pin "12") (pinfunction "VIND+_12") (pintype "input"))
      (node (ref "IC7") (pin "3") (pinfunction "VINA+_3") (pintype "input"))
      (node (ref "IC7") (pin "5") (pinfunction "VINB+_5") (pintype "input"))
      (node (ref "IC8") (pin "1") (pinfunction "X4_1") (pintype "bidirectional"))
      (node (ref "IC8") (pin "2") (pinfunction "X6_2") (pintype "bidirectional"))
      (node (ref "IC8") (pin "4") (pinfunction "X7_4") (pintype "bidirectional"))
      (node (ref "IC8") (pin "5") (pinfunction "X5_5") (pintype "bidirectional"))
      (node (ref "IC8") (pin "7") (pinfunction "VEE_7") (pintype "power_in"))
      (node (ref "IC8") (pin "8") (pinfunction "GND_8") (pintype "power_in"))
      (node (ref "IC9") (pin "3") (pinfunction "VINA+_3") (pintype "input"))
      (node (ref "IC9") (pin "4") (pinfunction "VSS_4") (pintype "power_in"))
      (node (ref "IC9") (pin "5") (pinfunction "VINB+_5") (pintype "input"))
      (node (ref "J1") (pin "P$3") (pinfunction "1_P$3") (pintype "passive"))
      (node (ref "J10") (pin "GND") (pinfunction "GND_GND") (pintype "passive"))
      (node (ref "J11") (pin "GND") (pinfunction "GND_GND") (pintype "passive"))
      (node (ref "J12") (pin "GND") (pinfunction "GND_GND") (pintype "passive"))
      (node (ref "J13") (pin "GND") (pinfunction "GND_GND") (pintype "passive"))
      (node (ref "J14") (pin "GND") (pinfunction "GND_GND") (pintype "passive"))
      (node (ref "J15") (pin "GND") (pinfunction "GND_GND") (pintype "passive"))
      (node (ref "J16") (pin "GND") (pinfunction "GND_GND") (pintype "passive"))
      (node (ref "J17") (pin "GND") (pinfunction "GND_GND") (pintype "passive"))
      (node (ref "J18") (pin "GND") (pinfunction "GND_GND") (pintype "passive"))
      (node (ref "J2") (pin "P$3") (pinfunction "1_P$3") (pintype "passive"))
      (node (ref "J3") (pin "P1") (pinfunction "1_P1") (pintype "passive"))
      (node (ref "J3") (pin "P2") (pinfunction "2_P2") (pintype "passive"))
      (node (ref "J4") (pin "P$3") (pinfunction "1_P$3") (pintype "passive"))
      (node (ref "J5") (pin "P1") (pinfunction "1_P1") (pintype "passive"))
      (node (ref "J6") (pin "P1") (pinfunction "1_P1") (pintype "passive"))
      (node (ref "J7") (pin "P1") (pinfunction "1_P1") (pintype "passive"))
      (node (ref "J8") (pin "P1") (pinfunction "1_P1") (pintype "passive"))
      (node (ref "J9") (pin "GND") (pinfunction "GND_GND") (pintype "passive"))
      (node (ref "JP1") (pin "3") (pinfunction "3_3") (pintype "passive"))
      (node (ref "JP1") (pin "5") (pinfunction "5_5") (pintype "passive"))
      (node (ref "JP1") (pin "9") (pinfunction "9_9") (pintype "passive"))
      (node (ref "JP3") (pin "3") (pinfunction "3_3") (pintype "passive"))
      (node (ref "JP3") (pin "4") (pinfunction "4_4") (pintype "passive"))
      (node (ref "JP3") (pin "5") (pinfunction "5_5") (pintype "passive"))
      (node (ref "JP3") (pin "6") (pinfunction "6_6") (pintype "passive"))
      (node (ref "JP3") (pin "7") (pinfunction "7_7") (pintype "passive"))
      (node (ref "JP3") (pin "8") (pinfunction "8_8") (pintype "passive"))
      (node (ref "LED1") (pin "K") (pinfunction "C_K") (pintype "passive"))
      (node (ref "LED2") (pin "K") (pinfunction "C_K") (pintype "passive"))
      (node (ref "Q1") (pin "GND") (pinfunction "GND_GND") (pintype "bidirectional"))
      (node (ref "Q2") (pin "E") (pinfunction "E_E") (pintype "passive"))
      (node (ref "R23") (pin "P$3") (pinfunction "A_P$3") (pintype "passive"))
      (node (ref "R24") (pin "P$3") (pinfunction "A_P$3") (pintype "passive"))
      (node (ref "R25") (pin "P$3") (pinfunction "A_P$3") (pintype "passive"))
      (node (ref "R26") (pin "P$3") (pinfunction "A_P$3") (pintype "passive"))
      (node (ref "R3") (pin "P$3") (pinfunction "A_P$3") (pintype "passive"))
      (node (ref "R4") (pin "P$3") (pinfunction "A_P$3") (pintype "passive"))
      (node (ref "R5") (pin "P$3") (pinfunction "A_P$3") (pintype "passive"))
      (node (ref "R50") (pin "1") (pinfunction "1_1") (pintype "passive"))
      (node (ref "R59") (pin "1") (pinfunction "1_1") (pintype "passive"))
      (node (ref "R6") (pin "P$3") (pinfunction "A_P$3") (pintype "passive"))
      (node (ref "R61") (pin "P$3") (pinfunction "A_P$3") (pintype "passive"))
      (node (ref "R62") (pin "P$3") (pinfunction "A_P$3") (pintype "passive"))
      (node (ref "R63") (pin "P$3") (pinfunction "A_P$3") (pintype "passive"))
      (node (ref "R64") (pin "P$3") (pinfunction "A_P$3") (pintype "passive"))
      (node (ref "R65") (pin "P$3") (pinfunction "A_P$3") (pintype "passive"))
      (node (ref "R66") (pin "P$3") (pinfunction "A_P$3") (pintype "passive"))
      (node (ref "R69") (pin "1") (pinfunction "1_1") (pintype "passive"))
      (node (ref "R7") (pin "P$3") (pinfunction "A_P$3") (pintype "passive"))
      (node (ref "R74") (pin "1") (pinfunction "1_1") (pintype "passive"))
      (node (ref "R76") (pin "P$3") (pinfunction "A_P$3") (pintype "passive"))
      (node (ref "R77") (pin "P$3") (pinfunction "A_P$3") (pintype "passive"))
      (node (ref "R78") (pin "P$3") (pinfunction "A_P$3") (pintype "passive"))
      (node (ref "R79") (pin "P$3") (pinfunction "A_P$3") (pintype "passive"))
      (node (ref "R8") (pin "P$3") (pinfunction "A_P$3") (pintype "passive"))
      (node (ref "R80") (pin "P$3") (pinfunction "A_P$3") (pintype "passive"))
      (node (ref "R81") (pin "P$3") (pinfunction "A_P$3") (pintype "passive"))
      (node (ref "R82") (pin "P$3") (pinfunction "A_P$3") (pintype "passive"))
      (node (ref "R83") (pin "P$3") (pinfunction "A_P$3") (pintype "passive"))
      (node (ref "R84") (pin "P$3") (pinfunction "A_P$3") (pintype "passive"))
      (node (ref "R85") (pin "P$3") (pinfunction "A_P$3") (pintype "passive"))
      (node (ref "R87") (pin "1") (pinfunction "1_1") (pintype "passive"))
      (node (ref "R9") (pin "P$3") (pinfunction "A_P$3") (pintype "passive"))
      (node (ref "U$1") (pin "3") (pinfunction "2_3") (pintype "bidirectional"))
      (node (ref "U$1") (pin "4") (pinfunction "4_4") (pintype "bidirectional"))
      (node (ref "U$1") (pin "K") (pinfunction "C_K") (pintype "passive"))
    )
    (net (code "28") (name "I2C_SCL") (class "Default")
      (node (ref "IC10") (pin "29") (pinfunction "PB10/SPI2_SCK/I2S_SCK/I2C2_SCL/USART3_TX_29") (pintype "bidirectional"))
      (node (ref "IC12") (pin "24") (pinfunction "SCLK_24") (pintype "bidirectional"))
      (node (ref "R52") (pin "1") (pinfunction "1_1") (pintype "passive"))
    )
    (net (code "29") (name "I2C_SDA") (class "Default")
      (node (ref "IC10") (pin "30") (pinfunction "PB11/I2C2_SDA/USART3_RX_30") (pintype "bidirectional"))
      (node (ref "IC12") (pin "23") (pinfunction "SDIN_23") (pintype "bidirectional"))
      (node (ref "R53") (pin "1") (pinfunction "1_1") (pintype "passive"))
    )
    (net (code "30") (name "I2S_LRCK") (class "Default")
      (node (ref "IC10") (pin "33") (pinfunction "PB12/SPI2_NSS/I2S2_WS/I2C2_SMBA/USART3_CK/TIM1_BKIN_33") (pintype "bidirectional"))
      (node (ref "IC12") (pin "5") (pinfunction "DACLRC_5") (pintype "bidirectional"))
      (node (ref "IC12") (pin "7") (pinfunction "ADCLRC_7") (pintype "bidirectional"))
    )
    (net (code "31") (name "I2S_MCK") (class "Default")
      (node (ref "IC10") (pin "37") (pinfunction "PC6/I2S2_MCK_37") (pintype "bidirectional"))
      (node (ref "IC12") (pin "25") (pinfunction "XTI/MCLK_25") (pintype "bidirectional"))
    )
    (net (code "32") (name "I2S_SCK") (class "Default")
      (node (ref "IC10") (pin "34") (pinfunction "PB13/SPI2_SCK/I2S2_SCK/USART3_CTS/TIM1_CH1N_34") (pintype "bidirectional"))
      (node (ref "IC12") (pin "3") (pinfunction "BCLK_3") (pintype "bidirectional"))
    )
    (net (code "33") (name "I2S_SIN") (class "Default")
      (node (ref "IC10") (pin "35") (pinfunction "PB14/SPI2_MISO/USART3_RTS/TIM1_CH2N_35") (pintype "bidirectional"))
      (node (ref "IC12") (pin "6") (pinfunction "ADCDAT_6") (pintype "bidirectional"))
    )
    (net (code "34") (name "I2S_SOUT") (class "Default")
      (node (ref "IC10") (pin "36") (pinfunction "PB15/SPI2_MOSI/I2S2_SD/TIM1_CH3N_36") (pintype "bidirectional"))
      (node (ref "IC12") (pin "4") (pinfunction "DACDAT_4") (pintype "bidirectional"))
    )
    (net (code "35") (name "JTCK") (class "Default")
      (node (ref "IC10") (pin "49") (pinfunction "PA14/JTCK-SWCLK_49") (pintype "bidirectional"))
      (node (ref "JP1") (pin "4") (pinfunction "4_4") (pintype "passive"))
    )
    (net (code "36") (name "JTDI") (class "Default")
      (node (ref "IC10") (pin "50") (pinfunction "PA15/JTDI/SPI3_NSS/I2S3_WS_50") (pintype "bidirectional"))
      (node (ref "JP1") (pin "8") (pinfunction "8_8") (pintype "passive"))
    )
    (net (code "37") (name "JTDO") (class "Default")
      (node (ref "IC10") (pin "55") (pinfunction "PB3/JTDO/SPI3_SCK/I2S3_SCK_55") (pintype "bidirectional"))
      (node (ref "JP1") (pin "6") (pinfunction "6_6") (pintype "passive"))
    )
    (net (code "38") (name "JTMS") (class "Default")
      (node (ref "IC10") (pin "46") (pinfunction "PA13/JTMS-SWDAT_46") (pintype "bidirectional"))
      (node (ref "JP1") (pin "2") (pinfunction "2_2") (pintype "passive"))
    )
    (net (code "39") (name "LED_GATE") (class "Default")
      (node (ref "IC10") (pin "38") (pinfunction "PC7/I2S3_MCK_38") (pintype "bidirectional"))
      (node (ref "R10") (pin "1") (pinfunction "1_1") (pintype "passive"))
      (node (ref "R90") (pin "1") (pinfunction "1_1") (pintype "passive"))
    )
    (net (code "40") (name "LIN") (class "Default")
      (node (ref "C56") (pin "+") (pinfunction "+_+") (pintype "passive"))
      (node (ref "IC12") (pin "20") (pinfunction "LLINEIN_20") (pintype "bidirectional"))
    )
    (net (code "41") (name "LOUT") (class "Default")
      (node (ref "C40") (pin "+") (pinfunction "+_+") (pintype "passive"))
      (node (ref "IC12") (pin "12") (pinfunction "LOUT_12") (pintype "bidirectional"))
    )
    (net (code "42") (name "Net-(C40-Pad-)") (class "Default")
      (node (ref "C40") (pin "-") (pinfunction "-_-") (pintype "passive"))
      (node (ref "R58") (pin "2") (pinfunction "2_2") (pintype "passive"))
      (node (ref "R59") (pin "2") (pinfunction "2_2") (pintype "passive"))
    )
    (net (code "43") (name "Net-(C53-Pad-)") (class "Default")
      (node (ref "C53") (pin "-") (pinfunction "-_-") (pintype "passive"))
      (node (ref "R68") (pin "2") (pinfunction "2_2") (pintype "passive"))
      (node (ref "R69") (pin "2") (pinfunction "2_2") (pintype "passive"))
    )
    (net (code "44") (name "Net-(C54-Pad1)") (class "Default")
      (node (ref "C54") (pin "1") (pinfunction "1_1") (pintype "passive"))
      (node (ref "C55") (pin "-") (pinfunction "-_-") (pintype "passive"))
      (node (ref "R74") (pin "2") (pinfunction "2_2") (pintype "passive"))
      (node (ref "R75") (pin "1") (pinfunction "1_1") (pintype "passive"))
    )
    (net (code "45") (name "Net-(C56-Pad-)") (class "Default")
      (node (ref "C56") (pin "-") (pinfunction "-_-") (pintype "passive"))
      (node (ref "C57") (pin "1") (pinfunction "1_1") (pintype "passive"))
      (node (ref "R86") (pin "1") (pinfunction "1_1") (pintype "passive"))
      (node (ref "R87") (pin "2") (pinfunction "2_2") (pintype "passive"))
    )
    (net (code "46") (name "Net-(D1-PadA)") (class "Default")
      (node (ref "D1") (pin "A") (pinfunction "A_A") (pintype "passive"))
      (node (ref "JP3") (pin "1") (pinfunction "1_1") (pintype "passive"))
      (node (ref "JP3") (pin "2") (pinfunction "2_2") (pintype "passive"))
    )
    (net (code "47") (name "Net-(D2-PadC)") (class "Default")
      (node (ref "D2") (pin "C") (pinfunction "C_C") (pintype "passive"))
      (node (ref "JP3") (pin "10") (pinfunction "10_10") (pintype "passive"))
      (node (ref "JP3") (pin "9") (pinfunction "9_9") (pintype "passive"))
    )
    (net (code "48") (name "Net-(IC2-VIN)") (class "Default")
      (node (ref "C4") (pin "1") (pinfunction "1_1") (pintype "passive"))
      (node (ref "IC2") (pin "3") (pinfunction "VIN_3") (pintype "input"))
      (node (ref "L2") (pin "2") (pinfunction "2_2") (pintype "passive"))
    )
    (net (code "49") (name "Net-(IC3A-X0)") (class "Default")
      (node (ref "IC3") (pin "13") (pinfunction "X0_13") (pintype "bidirectional"))
      (node (ref "R26") (pin "P$2") (pinfunction "S_P$2") (pintype "passive"))
    )
    (net (code "50") (name "Net-(IC3A-X1)") (class "Default")
      (node (ref "IC3") (pin "14") (pinfunction "X1_14") (pintype "bidirectional"))
      (node (ref "R9") (pin "P$2") (pinfunction "S_P$2") (pintype "passive"))
    )
    (net (code "51") (name "Net-(IC3A-X2)") (class "Default")
      (node (ref "IC3") (pin "15") (pinfunction "X2_15") (pintype "bidirectional"))
      (node (ref "R8") (pin "P$2") (pinfunction "S_P$2") (pintype "passive"))
    )
    (net (code "52") (name "Net-(IC3A-X3)") (class "Default")
      (node (ref "IC3") (pin "12") (pinfunction "X3_12") (pintype "bidirectional"))
      (node (ref "R66") (pin "P$2") (pinfunction "S_P$2") (pintype "passive"))
    )
    (net (code "53") (name "Net-(IC3A-X4)") (class "Default")
      (node (ref "IC3") (pin "1") (pinfunction "X4_1") (pintype "bidirectional"))
      (node (ref "R3") (pin "P$2") (pinfunction "S_P$2") (pintype "passive"))
    )
    (net (code "54") (name "Net-(IC3A-X5)") (class "Default")
      (node (ref "IC3") (pin "5") (pinfunction "X5_5") (pintype "bidirectional"))
      (node (ref "R5") (pin "P$2") (pinfunction "S_P$2") (pintype "passive"))
    )
    (net (code "55") (name "Net-(IC3A-X6)") (class "Default")
      (node (ref "IC3") (pin "2") (pinfunction "X6_2") (pintype "bidirectional"))
      (node (ref "R4") (pin "P$2") (pinfunction "S_P$2") (pintype "passive"))
    )
    (net (code "56") (name "Net-(IC3A-X7)") (class "Default")
      (node (ref "IC3") (pin "4") (pinfunction "X7_4") (pintype "bidirectional"))
      (node (ref "R25") (pin "P$2") (pinfunction "S_P$2") (pintype "passive"))
    )
    (net (code "57") (name "Net-(IC4-VIN)") (class "Default")
      (node (ref "C5") (pin "1") (pinfunction "1_1") (pintype "passive"))
      (node (ref "IC4") (pin "3") (pinfunction "VIN_3") (pintype "input"))
      (node (ref "L1") (pin "2") (pinfunction "2_2") (pintype "passive"))
    )
    (net (code "58") (name "Net-(IC5A-X0)") (class "Default")
      (node (ref "IC5") (pin "13") (pinfunction "X0_13") (pintype "bidirectional"))
      (node (ref "R83") (pin "P$2") (pinfunction "S_P$2") (pintype "passive"))
    )
    (net (code "59") (name "Net-(IC5A-X1)") (class "Default")
      (node (ref "IC5") (pin "14") (pinfunction "X1_14") (pintype "bidirectional"))
      (node (ref "R84") (pin "P$2") (pinfunction "S_P$2") (pintype "passive"))
    )
    (net (code "60") (name "Net-(IC5A-X2)") (class "Default")
      (node (ref "IC5") (pin "15") (pinfunction "X2_15") (pintype "bidirectional"))
      (node (ref "R85") (pin "P$2") (pinfunction "S_P$2") (pintype "passive"))
    )
    (net (code "61") (name "Net-(IC5A-X3)") (class "Default")
      (node (ref "IC5") (pin "12") (pinfunction "X3_12") (pintype "bidirectional"))
      (node (ref "R82") (pin "P$2") (pinfunction "S_P$2") (pintype "passive"))
    )
    (net (code "62") (name "Net-(IC5A-X4)") (class "Default")
      (node (ref "IC5") (pin "1") (pinfunction "X4_1") (pintype "bidirectional"))
      (node (ref "R23") (pin "P$2") (pinfunction "S_P$2") (pintype "passive"))
    )
    (net (code "63") (name "Net-(IC5A-X5)") (class "Default")
      (node (ref "IC5") (pin "5") (pinfunction "X5_5") (pintype "bidirectional"))
      (node (ref "R24") (pin "P$2") (pinfunction "S_P$2") (pintype "passive"))
    )
    (net (code "64") (name "Net-(IC5A-X6)") (class "Default")
      (node (ref "IC5") (pin "2") (pinfunction "X6_2") (pintype "bidirectional"))
      (node (ref "R6") (pin "P$2") (pinfunction "S_P$2") (pintype "passive"))
    )
    (net (code "65") (name "Net-(IC5A-X7)") (class "Default")
      (node (ref "IC5") (pin "4") (pinfunction "X7_4") (pintype "bidirectional"))
      (node (ref "R7") (pin "P$2") (pinfunction "S_P$2") (pintype "passive"))
    )
    (net (code "66") (name "Net-(IC6-VINA-)") (class "Default")
      (node (ref "C26") (pin "1") (pinfunction "1_1") (pintype "passive"))
      (node (ref "IC6") (pin "2") (pinfunction "VINA-_2") (pintype "input"))
      (node (ref "R30") (pin "2") (pinfunction "2_2") (pintype "passive"))
      (node (ref "R31") (pin "2") (pinfunction "2_2") (pintype "passive"))
      (node (ref "R34") (pin "1") (pinfunction "1_1") (pintype "passive"))
    )
    (net (code "67") (name "Net-(IC6-VINB-)") (class "Default")
      (node (ref "C27") (pin "1") (pinfunction "1_1") (pintype "passive"))
      (node (ref "IC6") (pin "6") (pinfunction "VINB-_6") (pintype "input"))
      (node (ref "R32") (pin "2") (pinfunction "2_2") (pintype "passive"))
      (node (ref "R33") (pin "2") (pinfunction "2_2") (pintype "passive"))
      (node (ref "R35") (pin "1") (pinfunction "1_1") (pintype "passive"))
    )
    (net (code "68") (name "Net-(IC6-VINC-)") (class "Default")
      (node (ref "C15") (pin "2") (pinfunction "2_2") (pintype "passive"))
      (node (ref "IC6") (pin "9") (pinfunction "VINC-_9") (pintype "input"))
      (node (ref "R12") (pin "2") (pinfunction "2_2") (pintype "passive"))
      (node (ref "R15") (pin "1") (pinfunction "1_1") (pintype "passive"))
      (node (ref "R16") (pin "1") (pinfunction "1_1") (pintype "passive"))
    )
    (net (code "69") (name "Net-(IC6-VIND-)") (class "Default")
      (node (ref "C14") (pin "2") (pinfunction "2_2") (pintype "passive"))
      (node (ref "IC6") (pin "13") (pinfunction "VIND-_13") (pintype "input"))
      (node (ref "R11") (pin "2") (pinfunction "2_2") (pintype "passive"))
      (node (ref "R13") (pin "1") (pinfunction "1_1") (pintype "passive"))
      (node (ref "R14") (pin "1") (pinfunction "1_1") (pintype "passive"))
    )
    (net (code "70") (name "Net-(IC7-VINA-)") (class "Default")
      (node (ref "C30") (pin "1") (pinfunction "1_1") (pintype "passive"))
      (node (ref "IC7") (pin "2") (pinfunction "VINA-_2") (pintype "input"))
      (node (ref "R40") (pin "2") (pinfunction "2_2") (pintype "passive"))
      (node (ref "R41") (pin "2") (pinfunction "2_2") (pintype "passive"))
      (node (ref "R46") (pin "1") (pinfunction "1_1") (pintype "passive"))
    )
    (net (code "71") (name "Net-(IC7-VINB-)") (class "Default")
      (node (ref "C28") (pin "1") (pinfunction "1_1") (pintype "passive"))
      (node (ref "IC7") (pin "6") (pinfunction "VINB-_6") (pintype "input"))
      (node (ref "R29") (pin "1") (pinfunction "1_1") (pintype "passive"))
      (node (ref "R42") (pin "2") (pinfunction "2_2") (pintype "passive"))
      (node (ref "R43") (pin "2") (pinfunction "2_2") (pintype "passive"))
    )
    (net (code "72") (name "Net-(IC7-VINC-)") (class "Default")
      (node (ref "C20") (pin "2") (pinfunction "2_2") (pintype "passive"))
      (node (ref "IC7") (pin "9") (pinfunction "VINC-_9") (pintype "input"))
      (node (ref "R18") (pin "2") (pinfunction "2_2") (pintype "passive"))
      (node (ref "R21") (pin "1") (pinfunction "1_1") (pintype "passive"))
      (node (ref "R22") (pin "1") (pinfunction "1_1") (pintype "passive"))
    )
    (net (code "73") (name "Net-(IC7-VIND-)") (class "Default")
      (node (ref "C19") (pin "2") (pinfunction "2_2") (pintype "passive"))
      (node (ref "IC7") (pin "13") (pinfunction "VIND-_13") (pintype "input"))
      (node (ref "R17") (pin "2") (pinfunction "2_2") (pintype "passive"))
      (node (ref "R19") (pin "1") (pinfunction "1_1") (pintype "passive"))
      (node (ref "R20") (pin "1") (pinfunction "1_1") (pintype "passive"))
    )
    (net (code "74") (name "Net-(IC8A-X0)") (class "Default")
      (node (ref "IC8") (pin "13") (pinfunction "X0_13") (pintype "bidirectional"))
      (node (ref "R79") (pin "P$2") (pinfunction "S_P$2") (pintype "passive"))
    )
    (net (code "75") (name "Net-(IC8A-X1)") (class "Default")
      (node (ref "IC8") (pin "14") (pinfunction "X1_14") (pintype "bidirectional"))
      (node (ref "R80") (pin "P$2") (pinfunction "S_P$2") (pintype "passive"))
    )
    (net (code "76") (name "Net-(IC8A-X2)") (class "Default")
      (node (ref "IC8") (pin "15") (pinfunction "X2_15") (pintype "bidirectional"))
      (node (ref "R81") (pin "P$2") (pinfunction "S_P$2") (pintype "passive"))
    )
    (net (code "77") (name "Net-(IC8A-X3)") (class "Default")
      (node (ref "IC8") (pin "12") (pinfunction "X3_12") (pintype "bidirectional"))
      (node (ref "R78") (pin "P$2") (pinfunction "S_P$2") (pintype "passive"))
    )
    (net (code "78") (name "Net-(IC9-VINA-)") (class "Default")
      (node (ref "C24") (pin "1") (pinfunction "1_1") (pintype "passive"))
      (node (ref "IC9") (pin "2") (pinfunction "VINA-_2") (pintype "input"))
      (node (ref "R27") (pin "1") (pinfunction "1_1") (pintype "passive"))
      (node (ref "R36") (pin "2") (pinfunction "2_2") (pintype "passive"))
      (node (ref "R37") (pin "2") (pinfunction "2_2") (pintype "passive"))
    )
    (net (code "79") (name "Net-(IC9-VINB-)") (class "Default")
      (node (ref "C25") (pin "2") (pinfunction "2_2") (pintype "passive"))
      (node (ref "IC9") (pin "6") (pinfunction "VINB-_6") (pintype "input"))
      (node (ref "R28") (pin "2") (pinfunction "2_2") (pintype "passive"))
      (node (ref "R38") (pin "1") (pinfunction "1_1") (pintype "passive"))
      (node (ref "R39") (pin "1") (pinfunction "1_1") (pintype "passive"))
    )
    (net (code "80") (name "Net-(IC10-PA8{slash}USART1_CK{slash}TIM1_CH1{slash}MCO)") (class "Default")
      (node (ref "IC10") (pin "41") (pinfunction "PA8/USART1_CK/TIM1_CH1/MCO_41") (pintype "bidirectional"))
      (node (ref "R47") (pin "1") (pinfunction "1_1") (pintype "passive"))
    )
    (net (code "81") (name "Net-(IC10-PA11{slash}USART1_CTS{slash}CANRX{slash}USBDM{slash}TIM1_CH4)") (class "Default")
      (node (ref "IC10") (pin "44") (pinfunction "PA11/USART1_CTS/CANRX/USBDM/TIM1_CH4_44") (pintype "bidirectional"))
      (node (ref "R44") (pin "1") (pinfunction "1_1") (pintype "passive"))
    )
    (net (code "82") (name "Net-(IC10-PD0{slash}OSC_IN)") (class "Default")
      (node (ref "IC10") (pin "5") (pinfunction "PD0/OSC_IN_5") (pintype "bidirectional"))
      (node (ref "Q1") (pin "X2") (pinfunction "X2_X2") (pintype "bidirectional"))
    )
    (net (code "83") (name "Net-(IC10-PD1{slash}OSC_OUT)") (class "Default")
      (node (ref "IC10") (pin "6") (pinfunction "PD1/OSC_OUT_6") (pintype "bidirectional"))
      (node (ref "Q1") (pin "X1") (pinfunction "X1_X1") (pintype "bidirectional"))
    )
    (net (code "84") (name "Net-(IC10-VCAP_1)") (class "Default")
      (node (ref "C31") (pin "1") (pinfunction "1_1") (pintype "passive"))
      (node (ref "IC10") (pin "31") (pinfunction "VCAP_1_31") (pintype "power_in"))
    )
    (net (code "85") (name "Net-(IC10-VCAP_2)") (class "Default")
      (node (ref "C35") (pin "1") (pinfunction "1_1") (pintype "passive"))
      (node (ref "IC10") (pin "47") (pinfunction "VCAP_2_47") (pintype "power_in"))
    )
    (net (code "86") (name "Net-(IC11A-X0)") (class "Default")
      (node (ref "IC11") (pin "13") (pinfunction "X0_13") (pintype "bidirectional"))
      (node (ref "R65") (pin "P$2") (pinfunction "S_P$2") (pintype "passive"))
    )
    (net (code "87") (name "Net-(IC11A-X1)") (class "Default")
      (node (ref "IC11") (pin "14") (pinfunction "X1_14") (pintype "bidirectional"))
      (node (ref "R76") (pin "P$2") (pinfunction "S_P$2") (pintype "passive"))
    )
    (net (code "88") (name "Net-(IC11A-X2)") (class "Default")
      (node (ref "IC11") (pin "15") (pinfunction "X2_15") (pintype "bidirectional"))
      (node (ref "R77") (pin "P$2") (pinfunction "S_P$2") (pintype "passive"))
    )
    (net (code "89") (name "Net-(IC11A-X4)") (class "Default")
      (node (ref "IC11") (pin "1") (pinfunction "X4_1") (pintype "bidirectional"))
      (node (ref "R64") (pin "P$2") (pinfunction "S_P$2") (pintype "passive"))
    )
    (net (code "90") (name "Net-(IC11A-X5)") (class "Default")
      (node (ref "IC11") (pin "5") (pinfunction "X5_5") (pintype "bidirectional"))
      (node (ref "R61") (pin "P$2") (pinfunction "S_P$2") (pintype "passive"))
    )
    (net (code "91") (name "Net-(IC11A-X6)") (class "Default")
      (node (ref "IC11") (pin "2") (pinfunction "X6_2") (pintype "bidirectional"))
      (node (ref "R63") (pin "P$2") (pinfunction "S_P$2") (pintype "passive"))
    )
    (net (code "92") (name "Net-(IC11A-X7)") (class "Default")
      (node (ref "IC11") (pin "4") (pinfunction "X7_4") (pintype "bidirectional"))
      (node (ref "R62") (pin "P$2") (pinfunction "S_P$2") (pintype "passive"))
    )
    (net (code "93") (name "Net-(IC12-VMID)") (class "Default")
      (node (ref "C47") (pin "1") (pinfunction "1_1") (pintype "passive"))
      (node (ref "C52") (pin "+") (pinfunction "+_+") (pintype "passive"))
      (node (ref "IC12") (pin "16") (pinfunction "VMID_16") (pintype "bidirectional"))
    )
    (net (code "94") (name "Net-(IC13-VINA-)") (class "Default")
      (node (ref "IC13") (pin "1") (pinfunction "VOUTA_1") (pintype "output"))
      (node (ref "IC13") (pin "2") (pinfunction "VINA-_2") (pintype "input"))
    )
    (net (code "95") (name "Net-(IC13-VINB-)") (class "Default")
      (node (ref "C50") (pin "1") (pinfunction "1_1") (pintype "passive"))
      (node (ref "IC13") (pin "6") (pinfunction "VINB-_6") (pintype "input"))
      (node (ref "R70") (pin "2") (pinfunction "2_2") (pintype "passive"))
      (node (ref "R71") (pin "2") (pinfunction "2_2") (pintype "passive"))
      (node (ref "R73") (pin "1") (pinfunction "1_1") (pintype "passive"))
    )
    (net (code "96") (name "Net-(IC13-VINC-)") (class "Default")
      (node (ref "C42") (pin "2") (pinfunction "2_2") (pintype "passive"))
      (node (ref "IC13") (pin "9") (pinfunction "VINC-_9") (pintype "input"))
      (node (ref "R49") (pin "2") (pinfunction "2_2") (pintype "passive"))
      (node (ref "R56") (pin "1") (pinfunction "1_1") (pintype "passive"))
      (node (ref "R57") (pin "1") (pinfunction "1_1") (pintype "passive"))
    )
    (net (code "97") (name "Net-(IC13-VIND-)") (class "Default")
      (node (ref "C41") (pin "2") (pinfunction "2_2") (pintype "passive"))
      (node (ref "IC13") (pin "13") (pinfunction "VIND-_13") (pintype "input"))
      (node (ref "R48") (pin "2") (pinfunction "2_2") (pintype "passive"))
      (node (ref "R54") (pin "1") (pinfunction "1_1") (pintype "passive"))
      (node (ref "R55") (pin "1") (pinfunction "1_1") (pintype "passive"))
    )
    (net (code "98") (name "Net-(IC14A--IN)") (class "Default")
      (node (ref "C49") (pin "1") (pinfunction "1_1") (pintype "passive"))
      (node (ref "IC14") (pin "2") (pinfunction "-IN_2") (pintype "input"))
      (node (ref "R68") (pin "1") (pinfunction "1_1") (pintype "passive"))
      (node (ref "R72") (pin "2") (pinfunction "2_2") (pintype "passive"))
    )
    (net (code "99") (name "Net-(IC14A-OUT)") (class "Default")
      (node (ref "C49") (pin "2") (pinfunction "2_2") (pintype "passive"))
      (node (ref "IC14") (pin "1") (pinfunction "OUT_1") (pintype "output"))
      (node (ref "R72") (pin "1") (pinfunction "1_1") (pintype "passive"))
      (node (ref "R89") (pin "2") (pinfunction "2_2") (pintype "passive"))
    )
    (net (code "100") (name "Net-(IC14B--IN)") (class "Default")
      (node (ref "C43") (pin "1") (pinfunction "1_1") (pintype "passive"))
      (node (ref "IC14") (pin "6") (pinfunction "-IN_6") (pintype "input"))
      (node (ref "R51") (pin "2") (pinfunction "2_2") (pintype "passive"))
      (node (ref "R58") (pin "1") (pinfunction "1_1") (pintype "passive"))
    )
    (net (code "101") (name "Net-(IC14B-OUT)") (class "Default")
      (node (ref "C43") (pin "2") (pinfunction "2_2") (pintype "passive"))
      (node (ref "IC14") (pin "7") (pinfunction "OUT_7") (pintype "output"))
      (node (ref "R51") (pin "1") (pinfunction "1_1") (pintype "passive"))
      (node (ref "R88") (pin "2") (pinfunction "2_2") (pintype "passive"))
    )
    (net (code "102") (name "Net-(J1-2)") (class "Default")
      (node (ref "J1") (pin "P$1") (pinfunction "2_P$1") (pintype "passive"))
      (node (ref "R36") (pin "1") (pinfunction "1_1") (pintype "passive"))
    )
    (net (code "103") (name "Net-(J2-2)") (class "Default")
      (node (ref "J2") (pin "P$1") (pinfunction "2_P$1") (pintype "passive"))
      (node (ref "R39") (pin "2") (pinfunction "2_2") (pintype "passive"))
    )
    (net (code "104") (name "Net-(J3-3)") (class "Default")
      (node (ref "J3") (pin "P3") (pinfunction "3_P3") (pintype "passive"))
      (node (ref "R67") (pin "1") (pinfunction "1_1") (pintype "passive"))
    )
    (net (code "105") (name "Net-(J4-2)") (class "Default")
      (node (ref "J4") (pin "P$1") (pinfunction "2_P$1") (pintype "passive"))
      (node (ref "R30") (pin "1") (pinfunction "1_1") (pintype "passive"))
    )
    (net (code "106") (name "Net-(J5-3)") (class "Default")
      (node (ref "J5") (pin "P3") (pinfunction "3_P3") (pintype "passive"))
      (node (ref "R75") (pin "2") (pinfunction "2_2") (pintype "passive"))
    )
    (net (code "107") (name "Net-(J6-3)") (class "Default")
      (node (ref "J6") (pin "P3") (pinfunction "3_P3") (pintype "passive"))
      (node (ref "R86") (pin "2") (pinfunction "2_2") (pintype "passive"))
    )
    (net (code "108") (name "Net-(J7-3)") (class "Default")
      (node (ref "J7") (pin "P3") (pinfunction "3_P3") (pintype "passive"))
      (node (ref "R88") (pin "1") (pinfunction "1_1") (pintype "passive"))
    )
    (net (code "109") (name "Net-(J8-3)") (class "Default")
      (node (ref "J8") (pin "P3") (pinfunction "3_P3") (pintype "passive"))
      (node (ref "R89") (pin "1") (pinfunction "1_1") (pintype "passive"))
    )
    (net (code "110") (name "Net-(J9-PadTIP)") (class "Default")
      (node (ref "J9") (pin "TIP") (pinfunction "TIP_TIP") (pintype "passive"))
      (node (ref "R13") (pin "2") (pinfunction "2_2") (pintype "passive"))
    )
    (net (code "111") (name "Net-(J10-PadTIP)") (class "Default")
      (node (ref "J10") (pin "TIP") (pinfunction "TIP_TIP") (pintype "passive"))
      (node (ref "R16") (pin "2") (pinfunction "2_2") (pintype "passive"))
    )
    (net (code "112") (name "Net-(J11-PadTIP)") (class "Default")
      (node (ref "J11") (pin "TIP") (pinfunction "TIP_TIP") (pintype "passive"))
      (node (ref "R33") (pin "1") (pinfunction "1_1") (pintype "passive"))
    )
    (net (code "113") (name "Net-(J12-PadTIP)") (class "Default")
      (node (ref "J12") (pin "TIP") (pinfunction "TIP_TIP") (pintype "passive"))
      (node (ref "R40") (pin "1") (pinfunction "1_1") (pintype "passive"))
    )
    (net (code "114") (name "Net-(J13-PadTIP)") (class "Default")
      (node (ref "J13") (pin "TIP") (pinfunction "TIP_TIP") (pintype "passive"))
      (node (ref "R19") (pin "2") (pinfunction "2_2") (pintype "passive"))
    )
    (net (code "115") (name "Net-(J14-PadTIP)") (class "Default")
      (node (ref "J14") (pin "TIP") (pinfunction "TIP_TIP") (pintype "passive"))
      (node (ref "R22") (pin "2") (pinfunction "2_2") (pintype "passive"))
    )
    (net (code "116") (name "Net-(J15-PadTIP)") (class "Default")
      (node (ref "J15") (pin "TIP") (pinfunction "TIP_TIP") (pintype "passive"))
      (node (ref "R43") (pin "1") (pinfunction "1_1") (pintype "passive"))
    )
    (net (code "117") (name "Net-(J16-PadTIP)") (class "Default")
      (node (ref "J16") (pin "TIP") (pinfunction "TIP_TIP") (pintype "passive"))
      (node (ref "R54") (pin "2") (pinfunction "2_2") (pintype "passive"))
    )
    (net (code "118") (name "Net-(J17-PadTIP)") (class "Default")
      (node (ref "J17") (pin "TIP") (pinfunction "TIP_TIP") (pintype "passive"))
      (node (ref "R57") (pin "2") (pinfunction "2_2") (pintype "passive"))
    )
    (net (code "119") (name "Net-(J18-PadTIP)") (class "Default")
      (node (ref "J18") (pin "TIP") (pinfunction "TIP_TIP") (pintype "passive"))
      (node (ref "R71") (pin "1") (pinfunction "1_1") (pintype "passive"))
    )
    (net (code "120") (name "Net-(LED1-PadA)") (class "Default")
      (node (ref "LED1") (pin "A") (pinfunction "A_A") (pintype "passive"))
      (node (ref "R47") (pin "2") (pinfunction "2_2") (pintype "passive"))
    )
    (net (code "121") (name "Net-(LED2-PadA)") (class "Default")
      (node (ref "LED2") (pin "A") (pinfunction "A_A") (pintype "passive"))
      (node (ref "R44") (pin "2") (pinfunction "2_2") (pintype "passive"))
    )
    (net (code "122") (name "Net-(Q2-PadB)") (class "Default")
      (node (ref "Q2") (pin "B") (pinfunction "B_B") (pintype "passive"))
      (node (ref "R67") (pin "2") (pinfunction "2_2") (pintype "passive"))
    )
    (net (code "123") (name "Net-(R10-Pad2)") (class "Default")
      (node (ref "R10") (pin "2") (pinfunction "2_2") (pintype "passive"))
      (node (ref "R90") (pin "2") (pinfunction "2_2") (pintype "passive"))
      (node (ref "U$1") (pin "A") (pinfunction "A_A") (pintype "passive"))
    )
    (net (code "124") (name "RESET") (class "Default")
      (node (ref "IC10") (pin "7") (pinfunction "NRST_7") (pintype "bidirectional"))
      (node (ref "JP1") (pin "10") (pinfunction "10_10") (pintype "passive"))
      (node (ref "R45") (pin "1") (pinfunction "1_1") (pintype "passive"))
    )
    (net (code "125") (name "RIN") (class "Default")
      (node (ref "C55") (pin "+") (pinfunction "+_+") (pintype "passive"))
      (node (ref "IC12") (pin "19") (pinfunction "RLINEIN_19") (pintype "bidirectional"))
    )
    (net (code "126") (name "ROUT") (class "Default")
      (node (ref "C53") (pin "+") (pinfunction "+_+") (pintype "passive"))
      (node (ref "IC12") (pin "13") (pinfunction "ROUT_13") (pintype "bidirectional"))
    )
    (net (code "127") (name "RX") (class "Default")
      (node (ref "IC10") (pin "43") (pinfunction "PA10/USART1_RX/TIM1_CH3_43") (pintype "bidirectional"))
    )
    (net (code "128") (name "SW_GATE") (class "Default")
      (node (ref "IC10") (pin "9") (pinfunction "PC1/ADC11_9") (pintype "bidirectional"))
      (node (ref "U$1") (pin "1") (pinfunction "3_1") (pintype "bidirectional"))
      (node (ref "U$1") (pin "2") (pinfunction "1_2") (pintype "bidirectional"))
    )
    (net (code "129") (name "TX") (class "Default")
      (node (ref "IC10") (pin "42") (pinfunction "PA9/USART1_TX/TIM1_CH2_42") (pintype "bidirectional"))
    )
    (net (code "130") (name "VBAT") (class "Default")
      (node (ref "IC10") (pin "1") (pinfunction "VBAT_1") (pintype "power_in"))
    )
    (net (code "131") (name "VCC") (class "Default")
      (node (ref "C3") (pin "+") (pinfunction "+_+") (pintype "passive"))
      (node (ref "C44") (pin "1") (pinfunction "1_1") (pintype "passive"))
      (node (ref "D1") (pin "C") (pinfunction "C_C") (pintype "passive"))
      (node (ref "IC14") (pin "8") (pinfunction "V+_8") (pintype "power_in"))
      (node (ref "L1") (pin "1") (pinfunction "1_1") (pintype "passive"))
      (node (ref "L2") (pin "1") (pinfunction "1_1") (pintype "passive"))
    )
    (net (code "132") (name "VEE") (class "Default")
      (node (ref "C1") (pin "-") (pinfunction "-_-") (pintype "passive"))
      (node (ref "C45") (pin "2") (pinfunction "2_2") (pintype "passive"))
      (node (ref "D2") (pin "A") (pinfunction "A_A") (pintype "passive"))
      (node (ref "IC14") (pin "4") (pinfunction "V-_4") (pintype "power_in"))
      (node (ref "R1") (pin "1") (pinfunction "1_1") (pintype "passive"))
      (node (ref "R2") (pin "1") (pinfunction "1_1") (pintype "passive"))
    )
    (net (code "133") (name "unconnected-(IC10-PA12{slash}USART1_RTS{slash}CANTX{slash}USBDP{slash}TIM1_ETR-Pad45)") (class "Default")
      (node (ref "IC10") (pin "45") (pinfunction "PA12/USART1_RTS/CANTX/USBDP/TIM1_ETR_45") (pintype "bidirectional"))
    )
    (net (code "134") (name "unconnected-(IC10-PB4{slash}NJTRST{slash}SPI3_MISO{slash}SPI1_MISO-Pad56)") (class "Default")
      (node (ref "IC10") (pin "56") (pinfunction "PB4/NJTRST/SPI3_MISO/SPI1_MISO_56") (pintype "bidirectional"))
    )
    (net (code "135") (name "unconnected-(IC10-PB9{slash}SPI2_NSS{slash}I2S2_WS{slash}I2C1_SDA{slash}TIM4_CH4-Pad62)") (class "Default")
      (node (ref "IC10") (pin "62") (pinfunction "PB9/SPI2_NSS/I2S2_WS/I2C1_SDA/TIM4_CH4_62") (pintype "bidirectional"))
    )
    (net (code "136") (name "unconnected-(IC10-PC8-Pad39)") (class "Default")
      (node (ref "IC10") (pin "39") (pinfunction "PC8_39") (pintype "bidirectional"))
    )
    (net (code "137") (name "unconnected-(IC10-PC9{slash}I2S2_CKIN{slash}I2S3_CKIN-Pad40)") (class "Default")
      (node (ref "IC10") (pin "40") (pinfunction "PC9/I2S2_CKIN/I2S3_CKIN_40") (pintype "bidirectional"))
    )
    (net (code "138") (name "unconnected-(IC10-PC10{slash}SPI3_SCK{slash}I2S3_SCK{slash}UART4_TX-Pad51)") (class "Default")
      (node (ref "IC10") (pin "51") (pinfunction "PC10/SPI3_SCK/I2S3_SCK/UART4_TX_51") (pintype "bidirectional"))
    )
    (net (code "139") (name "unconnected-(IC10-PC11{slash}UART4_RX{slash}SPI3_MISO{slash}USART3_RX-Pad52)") (class "Default")
      (node (ref "IC10") (pin "52") (pinfunction "PC11/UART4_RX/SPI3_MISO/USART3_RX_52") (pintype "bidirectional"))
    )
    (net (code "140") (name "unconnected-(IC10-PC12{slash}UART5_TX{slash}I2S3_SD{slash}USART3_CK-Pad53)") (class "Default")
      (node (ref "IC10") (pin "53") (pinfunction "PC12/UART5_TX/I2S3_SD/USART3_CK_53") (pintype "bidirectional"))
    )
    (net (code "141") (name "unconnected-(IC10-PD2{slash}TIM3-ETR-Pad54)") (class "Default")
      (node (ref "IC10") (pin "54") (pinfunction "PD2/TIM3-ETR_54") (pintype "bidirectional"))
    )
    (net (code "142") (name "unconnected-(IC12-CLKOUT-Pad2)") (class "Default")
      (node (ref "IC12") (pin "2") (pinfunction "CLKOUT_2") (pintype "bidirectional"))
    )
    (net (code "143") (name "unconnected-(IC12-LHPOUT-Pad9)") (class "Default")
      (node (ref "IC12") (pin "9") (pinfunction "LHPOUT_9") (pintype "bidirectional"))
    )
    (net (code "144") (name "unconnected-(IC12-MICBIAS-Pad17)") (class "Default")
      (node (ref "IC12") (pin "17") (pinfunction "MICBIAS_17") (pintype "bidirectional"))
    )
    (net (code "145") (name "unconnected-(IC12-MICIN-Pad18)") (class "Default")
      (node (ref "IC12") (pin "18") (pinfunction "MICIN_18") (pintype "bidirectional"))
    )
    (net (code "146") (name "unconnected-(IC12-RHPOUT-Pad10)") (class "Default")
      (node (ref "IC12") (pin "10") (pinfunction "RHPOUT_10") (pintype "bidirectional"))
    )
    (net (code "147") (name "unconnected-(IC12-XTO-Pad26)") (class "Default")
      (node (ref "IC12") (pin "26") (pinfunction "XTO_26") (pintype "bidirectional"))
    )
    (net (code "148") (name "unconnected-(J1-3-PadP$2)") (class "Default")
      (node (ref "J1") (pin "P$2") (pinfunction "3_P$2") (pintype "passive"))
    )
    (net (code "149") (name "unconnected-(J2-3-PadP$2)") (class "Default")
      (node (ref "J2") (pin "P$2") (pinfunction "3_P$2") (pintype "passive"))
    )
    (net (code "150") (name "unconnected-(J4-3-PadP$2)") (class "Default")
      (node (ref "J4") (pin "P$2") (pinfunction "3_P$2") (pintype "passive"))
    )
    (net (code "151") (name "unconnected-(J5-2-PadP2)") (class "Default")
      (node (ref "J5") (pin "P2") (pinfunction "2_P2") (pintype "passive"))
    )
    (net (code "152") (name "unconnected-(J6-2-PadP2)") (class "Default")
      (node (ref "J6") (pin "P2") (pinfunction "2_P2") (pintype "passive"))
    )
    (net (code "153") (name "unconnected-(J7-2-PadP2)") (class "Default")
      (node (ref "J7") (pin "P2") (pinfunction "2_P2") (pintype "passive"))
    )
    (net (code "154") (name "unconnected-(J8-2-PadP2)") (class "Default")
      (node (ref "J8") (pin "P2") (pinfunction "2_P2") (pintype "passive"))
    )
    (net (code "155") (name "unconnected-(J9-PadNORM)") (class "Default")
      (node (ref "J9") (pin "NORM") (pinfunction "NORM_NORM") (pintype "passive"))
    )
    (net (code "156") (name "unconnected-(J10-PadNORM)") (class "Default")
      (node (ref "J10") (pin "NORM") (pinfunction "NORM_NORM") (pintype "passive"))
    )
    (net (code "157") (name "unconnected-(J11-PadNORM)") (class "Default")
      (node (ref "J11") (pin "NORM") (pinfunction "NORM_NORM") (pintype "passive"))
    )
    (net (code "158") (name "unconnected-(J12-PadNORM)") (class "Default")
      (node (ref "J12") (pin "NORM") (pinfunction "NORM_NORM") (pintype "passive"))
    )
    (net (code "159") (name "unconnected-(J13-PadNORM)") (class "Default")
      (node (ref "J13") (pin "NORM") (pinfunction "NORM_NORM") (pintype "passive"))
    )
    (net (code "160") (name "unconnected-(J14-PadNORM)") (class "Default")
      (node (ref "J14") (pin "NORM") (pinfunction "NORM_NORM") (pintype "passive"))
    )
    (net (code "161") (name "unconnected-(J15-PadNORM)") (class "Default")
      (node (ref "J15") (pin "NORM") (pinfunction "NORM_NORM") (pintype "passive"))
    )
    (net (code "162") (name "unconnected-(J16-PadNORM)") (class "Default")
      (node (ref "J16") (pin "NORM") (pinfunction "NORM_NORM") (pintype "passive"))
    )
    (net (code "163") (name "unconnected-(J17-PadNORM)") (class "Default")
      (node (ref "J17") (pin "NORM") (pinfunction "NORM_NORM") (pintype "passive"))
    )
    (net (code "164") (name "unconnected-(J18-PadNORM)") (class "Default")
      (node (ref "J18") (pin "NORM") (pinfunction "NORM_NORM") (pintype "passive"))
    )
    (net (code "165") (name "unconnected-(JP1-Pad7)") (class "Default")
      (node (ref "JP1") (pin "7") (pinfunction "7_7") (pintype "passive"))
    )
  )
)
